# faout.net
KiCad netlist of a schematic drawn in EAGLE
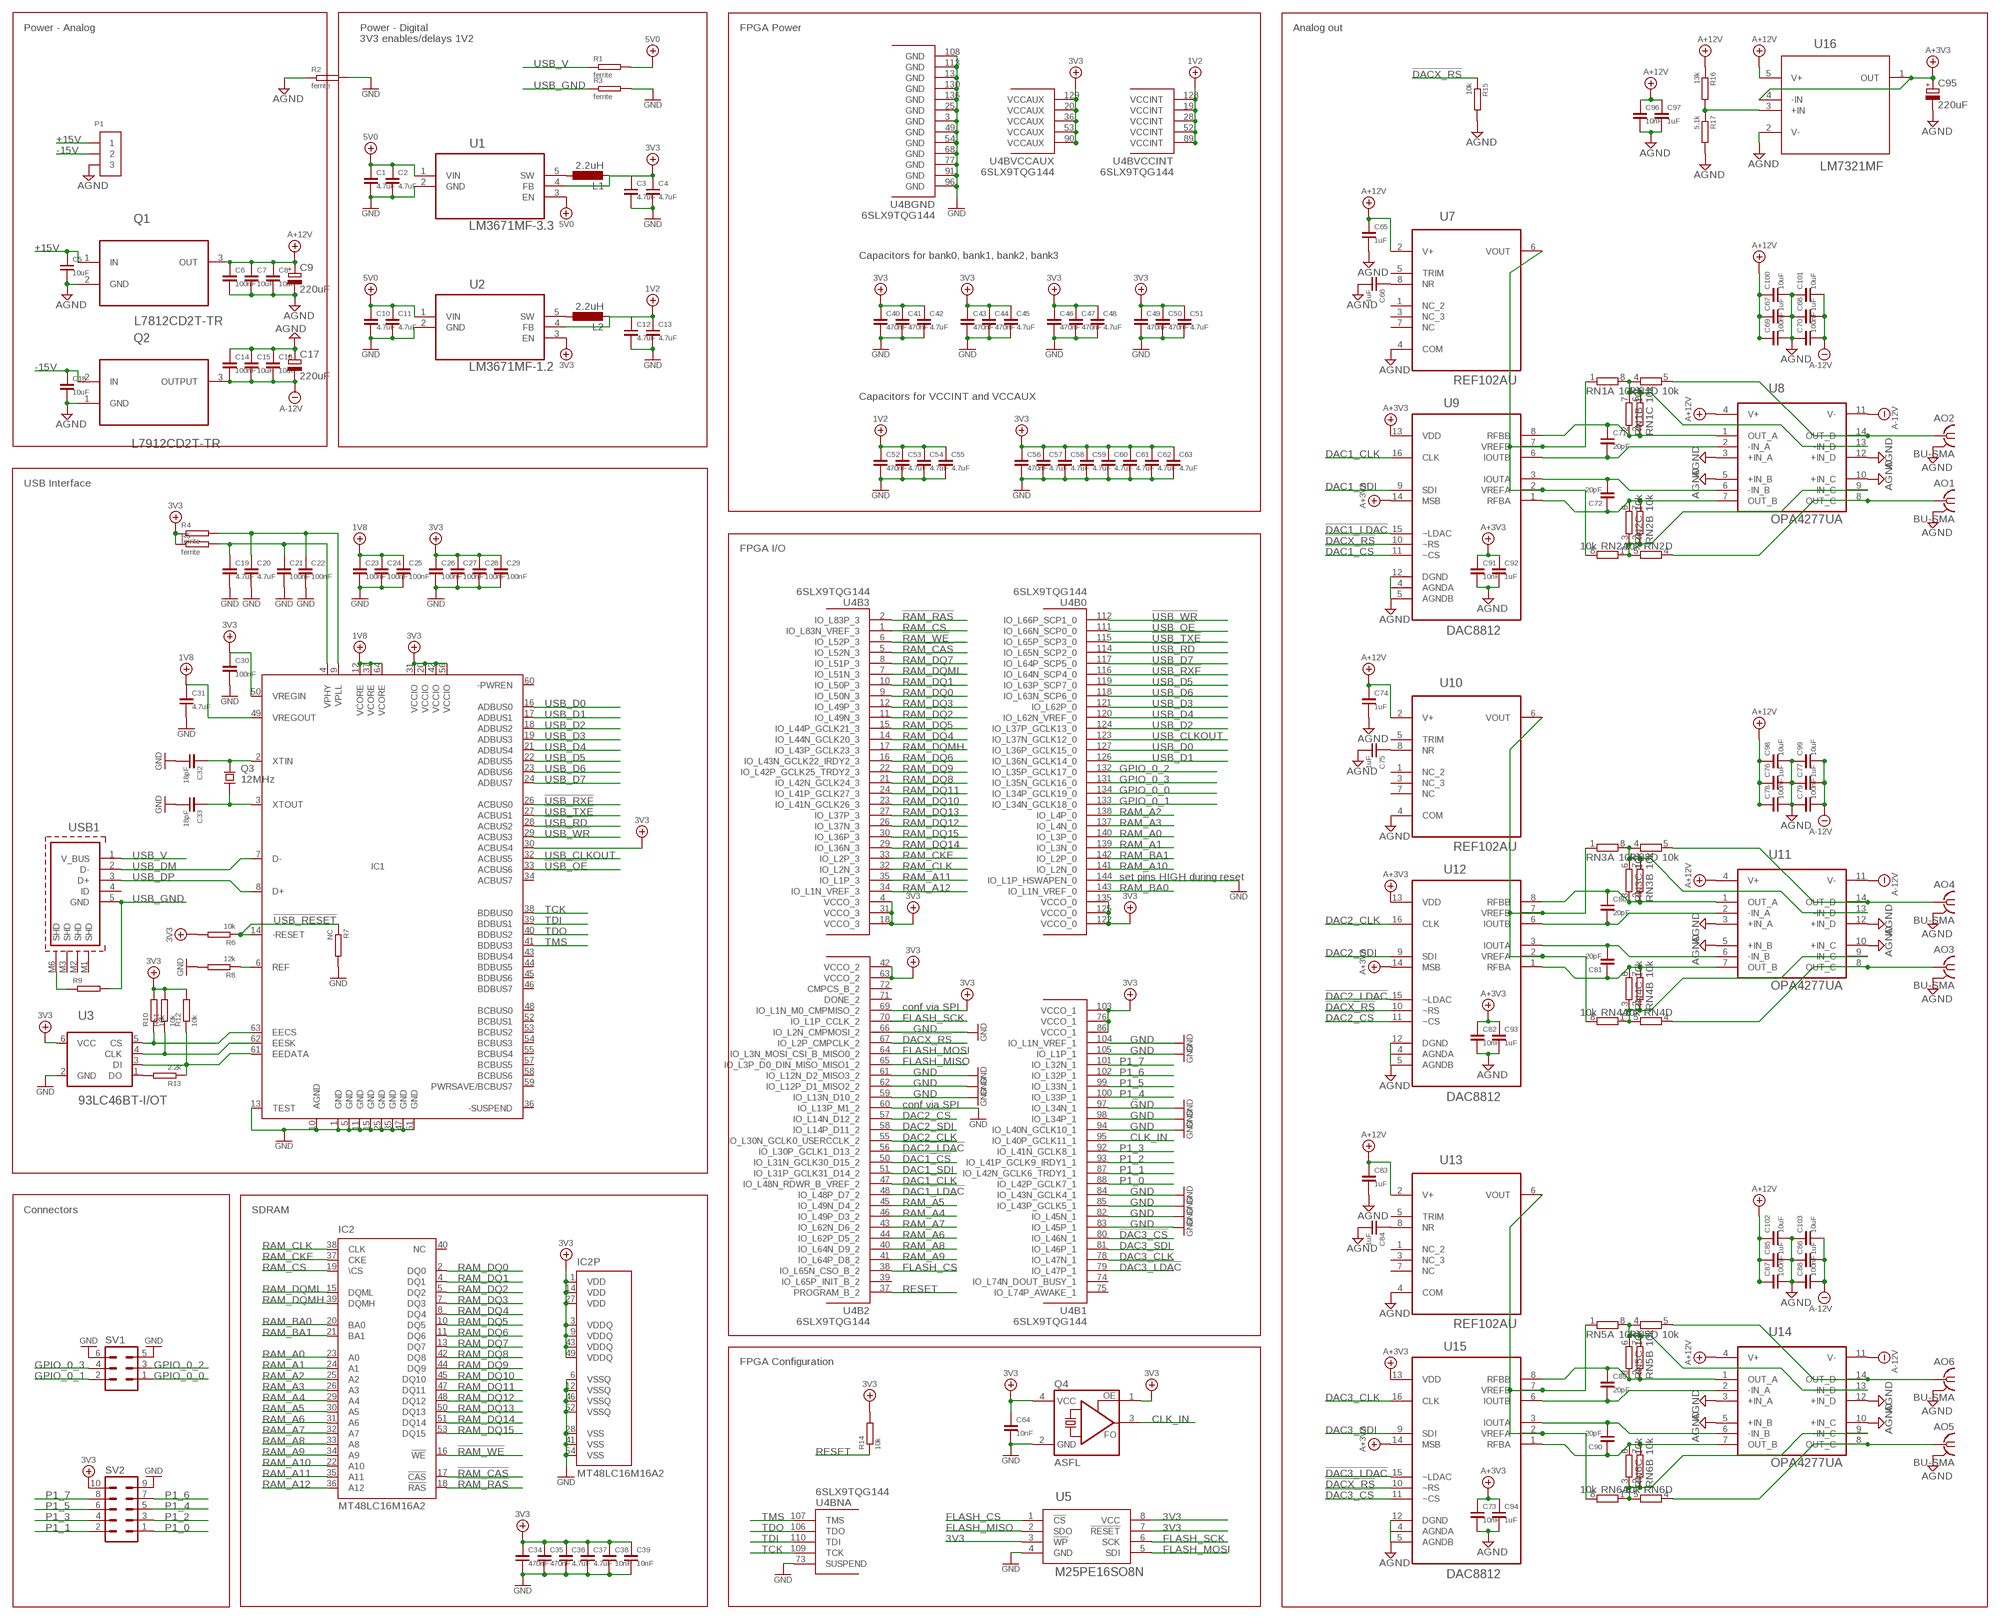
[diagram p0: schematic, sheet 1]

(export (version "E")
  (design (tool "Eeschema 10.0.6"))
  (components
    (comp (ref "AO1")
      (value "BU-SMA")
      (footprint "eagle-import:BU-SMA-H")
      (libsource (lib "eagle-import") (part "BU-SMA"))
    )
    (comp (ref "AO2")
      (value "BU-SMA")
      (footprint "eagle-import:BU-SMA-H")
      (libsource (lib "eagle-import") (part "BU-SMA"))
    )
    (comp (ref "AO3")
      (value "BU-SMA")
      (footprint "eagle-import:BU-SMA-H")
      (libsource (lib "eagle-import") (part "BU-SMA"))
    )
    (comp (ref "AO4")
      (value "BU-SMA")
      (footprint "eagle-import:BU-SMA-H")
      (libsource (lib "eagle-import") (part "BU-SMA"))
    )
    (comp (ref "AO5")
      (value "BU-SMA")
      (footprint "eagle-import:BU-SMA-H")
      (libsource (lib "eagle-import") (part "BU-SMA"))
    )
    (comp (ref "AO6")
      (value "BU-SMA")
      (footprint "eagle-import:BU-SMA-H")
      (libsource (lib "eagle-import") (part "BU-SMA"))
    )
    (comp (ref "C1")
      (value "4.7uF")
      (footprint "eagle-import:R0603")
      (libsource (lib "eagle-import") (part "C_EU0603"))
    )
    (comp (ref "C2")
      (value "4.7uF")
      (footprint "eagle-import:R0603")
      (libsource (lib "eagle-import") (part "C_EU0603"))
    )
    (comp (ref "C3")
      (value "4.7uF")
      (footprint "eagle-import:R0603")
      (libsource (lib "eagle-import") (part "C_EU0603"))
    )
    (comp (ref "C4")
      (value "4.7uF")
      (footprint "eagle-import:R0603")
      (libsource (lib "eagle-import") (part "C_EU0603"))
    )
    (comp (ref "C5")
      (value "10uF")
      (footprint "eagle-import:R0805")
      (libsource (lib "eagle-import") (part "C_EU0805"))
    )
    (comp (ref "C6")
      (value "100nF")
      (footprint "eagle-import:R0603")
      (libsource (lib "eagle-import") (part "C_EU0603"))
    )
    (comp (ref "C7")
      (value "10uF")
      (footprint "eagle-import:R0805")
      (libsource (lib "eagle-import") (part "C_EU0805"))
    )
    (comp (ref "C8")
      (value "10uF")
      (footprint "eagle-import:R0805")
      (libsource (lib "eagle-import") (part "C_EU0805"))
    )
    (comp (ref "C9")
      (value "220uF")
      (footprint "eagle-import:PANASONIC_E")
      (libsource (lib "eagle-import") (part "CPOL-EUE"))
    )
    (comp (ref "C10")
      (value "4.7uF")
      (footprint "eagle-import:R0603")
      (libsource (lib "eagle-import") (part "C_EU0603"))
    )
    (comp (ref "C11")
      (value "4.7uF")
      (footprint "eagle-import:R0603")
      (libsource (lib "eagle-import") (part "C_EU0603"))
    )
    (comp (ref "C12")
      (value "4.7uF")
      (footprint "eagle-import:R0603")
      (libsource (lib "eagle-import") (part "C_EU0603"))
    )
    (comp (ref "C13")
      (value "4.7uF")
      (footprint "eagle-import:R0603")
      (libsource (lib "eagle-import") (part "C_EU0603"))
    )
    (comp (ref "C14")
      (value "100nF")
      (footprint "eagle-import:R0603")
      (libsource (lib "eagle-import") (part "C_EU0603"))
    )
    (comp (ref "C15")
      (value "10uF")
      (footprint "eagle-import:R0805")
      (libsource (lib "eagle-import") (part "C_EU0805"))
    )
    (comp (ref "C16")
      (value "10uF")
      (footprint "eagle-import:R0805")
      (libsource (lib "eagle-import") (part "C_EU0805"))
    )
    (comp (ref "C17")
      (value "220uF")
      (footprint "eagle-import:PANASONIC_E")
      (libsource (lib "eagle-import") (part "CPOL-EUE"))
    )
    (comp (ref "C18")
      (value "10uF")
      (footprint "eagle-import:R0805")
      (libsource (lib "eagle-import") (part "C_EU0805"))
    )
    (comp (ref "C19")
      (value "4.7uF")
      (footprint "eagle-import:R0603")
      (libsource (lib "eagle-import") (part "C_EU0603"))
    )
    (comp (ref "C20")
      (value "4.7uF")
      (footprint "eagle-import:R0603")
      (libsource (lib "eagle-import") (part "C_EU0603"))
    )
    (comp (ref "C21")
      (value "100nF")
      (footprint "eagle-import:R0603")
      (libsource (lib "eagle-import") (part "C_EU0603"))
    )
    (comp (ref "C22")
      (value "100nF")
      (footprint "eagle-import:R0603")
      (libsource (lib "eagle-import") (part "C_EU0603"))
    )
    (comp (ref "C23")
      (value "100nF")
      (footprint "eagle-import:R0603")
      (libsource (lib "eagle-import") (part "C_EU0603"))
    )
    (comp (ref "C24")
      (value "100nF")
      (footprint "eagle-import:R0603")
      (libsource (lib "eagle-import") (part "C_EU0603"))
    )
    (comp (ref "C25")
      (value "100nF")
      (footprint "eagle-import:R0603")
      (libsource (lib "eagle-import") (part "C_EU0603"))
    )
    (comp (ref "C26")
      (value "100nF")
      (footprint "eagle-import:R0603")
      (libsource (lib "eagle-import") (part "C_EU0603"))
    )
    (comp (ref "C27")
      (value "100nF")
      (footprint "eagle-import:R0603")
      (libsource (lib "eagle-import") (part "C_EU0603"))
    )
    (comp (ref "C28")
      (value "100nF")
      (footprint "eagle-import:R0603")
      (libsource (lib "eagle-import") (part "C_EU0603"))
    )
    (comp (ref "C29")
      (value "100nF")
      (footprint "eagle-import:R0603")
      (libsource (lib "eagle-import") (part "C_EU0603"))
    )
    (comp (ref "C30")
      (value "100nF")
      (footprint "eagle-import:R0603")
      (libsource (lib "eagle-import") (part "C_EU0603"))
    )
    (comp (ref "C31")
      (value "4.7uF")
      (footprint "eagle-import:R0603")
      (libsource (lib "eagle-import") (part "C_EU0603"))
    )
    (comp (ref "C32")
      (value "18pF")
      (footprint "eagle-import:R0603")
      (libsource (lib "eagle-import") (part "C_EU0603"))
    )
    (comp (ref "C33")
      (value "18pF")
      (footprint "eagle-import:R0603")
      (libsource (lib "eagle-import") (part "C_EU0603"))
    )
    (comp (ref "C34")
      (value "470nF")
      (footprint "eagle-import:R0603")
      (libsource (lib "eagle-import") (part "C_EU0603"))
    )
    (comp (ref "C35")
      (value "470nF")
      (footprint "eagle-import:R0603")
      (libsource (lib "eagle-import") (part "C_EU0603"))
    )
    (comp (ref "C36")
      (value "4.7uF")
      (footprint "eagle-import:R0603")
      (libsource (lib "eagle-import") (part "C_EU0603"))
    )
    (comp (ref "C37")
      (value "4.7uF")
      (footprint "eagle-import:R0603")
      (libsource (lib "eagle-import") (part "C_EU0603"))
    )
    (comp (ref "C38")
      (value "10nF")
      (footprint "eagle-import:R0603")
      (libsource (lib "eagle-import") (part "C_EU0603"))
    )
    (comp (ref "C39")
      (value "10nF")
      (footprint "eagle-import:R0603")
      (libsource (lib "eagle-import") (part "C_EU0603"))
    )
    (comp (ref "C40")
      (value "470nF")
      (footprint "eagle-import:R0603")
      (libsource (lib "eagle-import") (part "C_EU0603"))
    )
    (comp (ref "C41")
      (value "470nF")
      (footprint "eagle-import:R0603")
      (libsource (lib "eagle-import") (part "C_EU0603"))
    )
    (comp (ref "C42")
      (value "4.7uF")
      (footprint "eagle-import:R0603")
      (libsource (lib "eagle-import") (part "C_EU0603"))
    )
    (comp (ref "C43")
      (value "470nF")
      (footprint "eagle-import:R0603")
      (libsource (lib "eagle-import") (part "C_EU0603"))
    )
    (comp (ref "C44")
      (value "470nF")
      (footprint "eagle-import:R0603")
      (libsource (lib "eagle-import") (part "C_EU0603"))
    )
    (comp (ref "C45")
      (value "4.7uF")
      (footprint "eagle-import:R0603")
      (libsource (lib "eagle-import") (part "C_EU0603"))
    )
    (comp (ref "C46")
      (value "470nF")
      (footprint "eagle-import:R0603")
      (libsource (lib "eagle-import") (part "C_EU0603"))
    )
    (comp (ref "C47")
      (value "470nF")
      (footprint "eagle-import:R0603")
      (libsource (lib "eagle-import") (part "C_EU0603"))
    )
    (comp (ref "C48")
      (value "4.7uF")
      (footprint "eagle-import:R0603")
      (libsource (lib "eagle-import") (part "C_EU0603"))
    )
    (comp (ref "C49")
      (value "470nF")
      (footprint "eagle-import:R0603")
      (libsource (lib "eagle-import") (part "C_EU0603"))
    )
    (comp (ref "C50")
      (value "470nF")
      (footprint "eagle-import:R0603")
      (libsource (lib "eagle-import") (part "C_EU0603"))
    )
    (comp (ref "C51")
      (value "4.7uF")
      (footprint "eagle-import:R0603")
      (libsource (lib "eagle-import") (part "C_EU0603"))
    )
    (comp (ref "C52")
      (value "470nF")
      (footprint "eagle-import:R0603")
      (libsource (lib "eagle-import") (part "C_EU0603"))
    )
    (comp (ref "C53")
      (value "4.7uF")
      (footprint "eagle-import:R0603")
      (libsource (lib "eagle-import") (part "C_EU0603"))
    )
    (comp (ref "C54")
      (value "4.7uF")
      (footprint "eagle-import:R0603")
      (libsource (lib "eagle-import") (part "C_EU0603"))
    )
    (comp (ref "C55")
      (value "4.7uF")
      (footprint "eagle-import:R0603")
      (libsource (lib "eagle-import") (part "C_EU0603"))
    )
    (comp (ref "C56")
      (value "470nF")
      (footprint "eagle-import:R0603")
      (libsource (lib "eagle-import") (part "C_EU0603"))
    )
    (comp (ref "C57")
      (value "4.7uF")
      (footprint "eagle-import:R0603")
      (libsource (lib "eagle-import") (part "C_EU0603"))
    )
    (comp (ref "C58")
      (value "4.7uF")
      (footprint "eagle-import:R0603")
      (libsource (lib "eagle-import") (part "C_EU0603"))
    )
    (comp (ref "C59")
      (value "4.7uF")
      (footprint "eagle-import:R0603")
      (libsource (lib "eagle-import") (part "C_EU0603"))
    )
    (comp (ref "C60")
      (value "4.7uF")
      (footprint "eagle-import:R0603")
      (libsource (lib "eagle-import") (part "C_EU0603"))
    )
    (comp (ref "C61")
      (value "4.7uF")
      (footprint "eagle-import:R0603")
      (libsource (lib "eagle-import") (part "C_EU0603"))
    )
    (comp (ref "C62")
      (value "4.7uF")
      (footprint "eagle-import:R0603")
      (libsource (lib "eagle-import") (part "C_EU0603"))
    )
    (comp (ref "C63")
      (value "4.7uF")
      (footprint "eagle-import:R0603")
      (libsource (lib "eagle-import") (part "C_EU0603"))
    )
    (comp (ref "C64")
      (value "10nF")
      (footprint "eagle-import:R0603")
      (libsource (lib "eagle-import") (part "C_EU0603"))
    )
    (comp (ref "C65")
      (value "1uF")
      (footprint "eagle-import:R0603")
      (libsource (lib "eagle-import") (part "C_EU0603"))
    )
    (comp (ref "C66")
      (value "1uF")
      (footprint "eagle-import:R0603")
      (libsource (lib "eagle-import") (part "C_EU0603"))
    )
    (comp (ref "C67")
      (value "1uF")
      (footprint "eagle-import:R0603")
      (libsource (lib "eagle-import") (part "C_EU0603"))
    )
    (comp (ref "C68")
      (value "1uF")
      (footprint "eagle-import:R0603")
      (libsource (lib "eagle-import") (part "C_EU0603"))
    )
    (comp (ref "C69")
      (value "100nF")
      (footprint "eagle-import:R0603")
      (libsource (lib "eagle-import") (part "C_EU0603"))
    )
    (comp (ref "C70")
      (value "100nF")
      (footprint "eagle-import:R0603")
      (libsource (lib "eagle-import") (part "C_EU0603"))
    )
    (comp (ref "C71")
      (value "20pF")
      (footprint "eagle-import:R0603")
      (libsource (lib "eagle-import") (part "C_EU0603"))
    )
    (comp (ref "C72")
      (value "20pF")
      (footprint "eagle-import:R0603")
      (libsource (lib "eagle-import") (part "C_EU0603"))
    )
    (comp (ref "C73")
      (value "10nF")
      (footprint "eagle-import:R0603")
      (libsource (lib "eagle-import") (part "C_EU0603"))
    )
    (comp (ref "C74")
      (value "1uF")
      (footprint "eagle-import:R0603")
      (libsource (lib "eagle-import") (part "C_EU0603"))
    )
    (comp (ref "C75")
      (value "1uF")
      (footprint "eagle-import:R0603")
      (libsource (lib "eagle-import") (part "C_EU0603"))
    )
    (comp (ref "C76")
      (value "1uF")
      (footprint "eagle-import:R0603")
      (libsource (lib "eagle-import") (part "C_EU0603"))
    )
    (comp (ref "C77")
      (value "1uF")
      (footprint "eagle-import:R0603")
      (libsource (lib "eagle-import") (part "C_EU0603"))
    )
    (comp (ref "C78")
      (value "100nF")
      (footprint "eagle-import:R0603")
      (libsource (lib "eagle-import") (part "C_EU0603"))
    )
    (comp (ref "C79")
      (value "100nF")
      (footprint "eagle-import:R0603")
      (libsource (lib "eagle-import") (part "C_EU0603"))
    )
    (comp (ref "C80")
      (value "20pF")
      (footprint "eagle-import:R0603")
      (libsource (lib "eagle-import") (part "C_EU0603"))
    )
    (comp (ref "C81")
      (value "20pF")
      (footprint "eagle-import:R0603")
      (libsource (lib "eagle-import") (part "C_EU0603"))
    )
    (comp (ref "C82")
      (value "10nF")
      (footprint "eagle-import:R0603")
      (libsource (lib "eagle-import") (part "C_EU0603"))
    )
    (comp (ref "C83")
      (value "1uF")
      (footprint "eagle-import:R0603")
      (libsource (lib "eagle-import") (part "C_EU0603"))
    )
    (comp (ref "C84")
      (value "1uF")
      (footprint "eagle-import:R0603")
      (libsource (lib "eagle-import") (part "C_EU0603"))
    )
    (comp (ref "C85")
      (value "1uF")
      (footprint "eagle-import:R0603")
      (libsource (lib "eagle-import") (part "C_EU0603"))
    )
    (comp (ref "C86")
      (value "1uF")
      (footprint "eagle-import:R0603")
      (libsource (lib "eagle-import") (part "C_EU0603"))
    )
    (comp (ref "C87")
      (value "100nF")
      (footprint "eagle-import:R0603")
      (libsource (lib "eagle-import") (part "C_EU0603"))
    )
    (comp (ref "C88")
      (value "100nF")
      (footprint "eagle-import:R0603")
      (libsource (lib "eagle-import") (part "C_EU0603"))
    )
    (comp (ref "C89")
      (value "20pF")
      (footprint "eagle-import:R0603")
      (libsource (lib "eagle-import") (part "C_EU0603"))
    )
    (comp (ref "C90")
      (value "20pF")
      (footprint "eagle-import:R0603")
      (libsource (lib "eagle-import") (part "C_EU0603"))
    )
    (comp (ref "C91")
      (value "10nF")
      (footprint "eagle-import:R0603")
      (libsource (lib "eagle-import") (part "C_EU0603"))
    )
    (comp (ref "C92")
      (value "1uF")
      (footprint "eagle-import:R0603")
      (libsource (lib "eagle-import") (part "C_EU0603"))
    )
    (comp (ref "C93")
      (value "1uF")
      (footprint "eagle-import:R0603")
      (libsource (lib "eagle-import") (part "C_EU0603"))
    )
    (comp (ref "C94")
      (value "1uF")
      (footprint "eagle-import:R0603")
      (libsource (lib "eagle-import") (part "C_EU0603"))
    )
    (comp (ref "C95")
      (value "220uF")
      (footprint "eagle-import:PANASONIC_E")
      (libsource (lib "eagle-import") (part "CPOL-EUE"))
    )
    (comp (ref "C96")
      (value "10nF")
      (footprint "eagle-import:R0603")
      (libsource (lib "eagle-import") (part "C_EU0603"))
    )
    (comp (ref "C97")
      (value "1uF")
      (footprint "eagle-import:R0603")
      (libsource (lib "eagle-import") (part "C_EU0603"))
    )
    (comp (ref "C98")
      (value "10uF")
      (footprint "eagle-import:R0805")
      (libsource (lib "eagle-import") (part "C_EU0805"))
    )
    (comp (ref "C99")
      (value "10uF")
      (footprint "eagle-import:R0805")
      (libsource (lib "eagle-import") (part "C_EU0805"))
    )
    (comp (ref "C100")
      (value "10uF")
      (footprint "eagle-import:R0805")
      (libsource (lib "eagle-import") (part "C_EU0805"))
    )
    (comp (ref "C101")
      (value "10uF")
      (footprint "eagle-import:R0805")
      (libsource (lib "eagle-import") (part "C_EU0805"))
    )
    (comp (ref "C102")
      (value "10uF")
      (footprint "eagle-import:R0805")
      (libsource (lib "eagle-import") (part "C_EU0805"))
    )
    (comp (ref "C103")
      (value "10uF")
      (footprint "eagle-import:R0805")
      (libsource (lib "eagle-import") (part "C_EU0805"))
    )
    (comp (ref "IC1")
      (value "FT2232HL")
      (footprint "eagle-import:TQFP64-12X12")
      (libsource (lib "eagle-import") (part "FT2232HL"))
    )
    (comp (ref "IC2")
      (value "MT48LC16M16A2")
      (footprint "eagle-import:TSOP54-400")
      (libsource (lib "eagle-import") (part "MT48LC16M16A2"))
    )
    (comp (ref "L1")
      (value "2.2uH")
      (footprint "eagle-import:L5038P")
      (libsource (lib "eagle-import") (part "L-EUL5038P"))
    )
    (comp (ref "L2")
      (value "2.2uH")
      (footprint "eagle-import:L5038P")
      (libsource (lib "eagle-import") (part "L-EUL5038P"))
    )
    (comp (ref "P1")
      (value "TE_CONN_MTE_HEADER3R")
      (footprint "eagle-import:TE_CONN_MTE_HEADER3_R")
      (libsource (lib "eagle-import") (part "TE_CONN_MTE_HEADER3R"))
    )
    (comp (ref "Q1")
      (value "L7812CD2T-TR")
      (footprint "eagle-import:TO254P1524X460-3N")
      (fields (field (name "OC_FARNELL") "2296017"))
      (libsource (lib "eagle-import") (part "L7812CD2T-TR"))
    )
    (comp (ref "Q2")
      (value "L7912CD2T-TR")
      (footprint "eagle-import:TO254P1524X460-3N")
      (libsource (lib "eagle-import") (part "L7912CD2T-TR"))
    )
    (comp (ref "Q3")
      (value "12MHz")
      (footprint "eagle-import:TXC_QUARTZ_7A")
      (libsource (lib "eagle-import") (part "TXC_QUARTZ_7A"))
    )
    (comp (ref "Q4")
      (value "ASFL")
      (footprint "eagle-import:ASF")
      (fields (field (name "MPN") "ASFLM1-50.000MHZ-C-T"))
      (libsource (lib "eagle-import") (part "ASFL"))
    )
    (comp (ref "R1")
      (value "ferrite")
      (footprint "eagle-import:R1206")
      (libsource (lib "eagle-import") (part "R_EU1206"))
    )
    (comp (ref "R2")
      (value "ferrite")
      (footprint "eagle-import:R1206")
      (libsource (lib "eagle-import") (part "R_EU1206"))
    )
    (comp (ref "R3")
      (value "ferrite")
      (footprint "eagle-import:R1206")
      (libsource (lib "eagle-import") (part "R_EU1206"))
    )
    (comp (ref "R4")
      (value "ferrite")
      (footprint "eagle-import:R0603")
      (libsource (lib "eagle-import") (part "R_EU0603"))
    )
    (comp (ref "R5")
      (value "ferrite")
      (footprint "eagle-import:R0603")
      (libsource (lib "eagle-import") (part "R_EU0603"))
    )
    (comp (ref "R6")
      (value "10k")
      (footprint "eagle-import:R0603")
      (libsource (lib "eagle-import") (part "R_EU0603"))
    )
    (comp (ref "R7")
      (value "NC")
      (footprint "eagle-import:R0603")
      (libsource (lib "eagle-import") (part "R_EU0603"))
    )
    (comp (ref "R8")
      (value "12k")
      (footprint "eagle-import:R0603")
      (libsource (lib "eagle-import") (part "R_EU0603"))
    )
    (comp (ref "R9")
      (value "R_EU0603")
      (footprint "eagle-import:R0603")
      (libsource (lib "eagle-import") (part "R_EU0603"))
    )
    (comp (ref "R10")
      (value "10k")
      (footprint "eagle-import:R0603")
      (libsource (lib "eagle-import") (part "R_EU0603"))
    )
    (comp (ref "R11")
      (value "10k")
      (footprint "eagle-import:R0603")
      (libsource (lib "eagle-import") (part "R_EU0603"))
    )
    (comp (ref "R12")
      (value "10k")
      (footprint "eagle-import:R0603")
      (libsource (lib "eagle-import") (part "R_EU0603"))
    )
    (comp (ref "R13")
      (value "2.2k")
      (footprint "eagle-import:R0603")
      (libsource (lib "eagle-import") (part "R_EU0603"))
    )
    (comp (ref "R14")
      (value "10k")
      (footprint "eagle-import:R0603")
      (libsource (lib "eagle-import") (part "R_EU0603"))
    )
    (comp (ref "R15")
      (value "10k")
      (footprint "eagle-import:R0603")
      (libsource (lib "eagle-import") (part "R_EU0603"))
    )
    (comp (ref "R16")
      (value "13k")
      (footprint "eagle-import:R0603")
      (libsource (lib "eagle-import") (part "R_EU0603"))
    )
    (comp (ref "R17")
      (value "5.1k")
      (footprint "eagle-import:R0603")
      (libsource (lib "eagle-import") (part "R_EU0603"))
    )
    (comp (ref "RN1")
      (value "10k")
      (footprint "eagle-import:EXBV8V")
      (fields (field (name "OC_FARNELL") "1560925"))
      (libsource (lib "eagle-import") (part "4R-NEXBV8V"))
    )
    (comp (ref "RN2")
      (value "10k")
      (footprint "eagle-import:EXBV8V")
      (fields (field (name "OC_FARNELL") "1560925"))
      (libsource (lib "eagle-import") (part "4R-NEXBV8V"))
    )
    (comp (ref "RN3")
      (value "10k")
      (footprint "eagle-import:EXBV8V")
      (fields (field (name "OC_FARNELL") "1560925"))
      (libsource (lib "eagle-import") (part "4R-NEXBV8V"))
    )
    (comp (ref "RN4")
      (value "10k")
      (footprint "eagle-import:EXBV8V")
      (fields (field (name "OC_FARNELL") "1560925"))
      (libsource (lib "eagle-import") (part "4R-NEXBV8V"))
    )
    (comp (ref "RN5")
      (value "10k")
      (footprint "eagle-import:EXBV8V")
      (fields (field (name "OC_FARNELL") "1560925"))
      (libsource (lib "eagle-import") (part "4R-NEXBV8V"))
    )
    (comp (ref "RN6")
      (value "10k")
      (footprint "eagle-import:EXBV8V")
      (fields (field (name "OC_FARNELL") "1560925"))
      (libsource (lib "eagle-import") (part "4R-NEXBV8V"))
    )
    (comp (ref "SV1")
      (value "ML6L")
      (footprint "eagle-import:ML6L")
      (fields (field (name "OC_FARNELL") "2356262"))
      (libsource (lib "eagle-import") (part "ML6L"))
    )
    (comp (ref "SV2")
      (value "ML10")
      (footprint "eagle-import:ML10")
      (libsource (lib "eagle-import") (part "ML10"))
    )
    (comp (ref "U1")
      (value "LM3671MF-3.3")
      (footprint "eagle-import:SOT95P284X122-5N")
      (libsource (lib "eagle-import") (part "LM3671MF-3.3"))
    )
    (comp (ref "U2")
      (value "LM3671MF-1.2")
      (footprint "eagle-import:SOT95P284X122-5N")
      (libsource (lib "eagle-import") (part "LM3671MF-1.2"))
    )
    (comp (ref "U3")
      (value "93LC46BT-I/OT")
      (footprint "eagle-import:SOT95P280X145-6N")
      (libsource (lib "eagle-import") (part "93LC46BT-I/OT"))
    )
    (comp (ref "U4")
      (value "6SLX9TQG144")
      (footprint "eagle-import:TQ144")
      (fields (field (name "OC_FARNELL") "1876228"))
      (libsource (lib "eagle-import") (part "6SLX9TQG144"))
    )
    (comp (ref "U5")
      (value "M25PE16SO8N")
      (footprint "eagle-import:SOIC127P600X175-8N")
      (libsource (lib "eagle-import") (part "M25PE16SO8N"))
    )
    (comp (ref "U7")
      (value "REF102AU")
      (footprint "eagle-import:SOIC127P600X175-8N")
      (libsource (lib "eagle-import") (part "REF102AU"))
    )
    (comp (ref "U8")
      (value "OPA4277UA")
      (footprint "eagle-import:SOIC127P600X175-14N")
      (libsource (lib "eagle-import") (part "OPA4277UA"))
    )
    (comp (ref "U9")
      (value "DAC8812")
      (footprint "eagle-import:SOP65P640X120-16N")
      (libsource (lib "eagle-import") (part "DAC8812"))
    )
    (comp (ref "U10")
      (value "REF102AU")
      (footprint "eagle-import:SOIC127P600X175-8N")
      (libsource (lib "eagle-import") (part "REF102AU"))
    )
    (comp (ref "U11")
      (value "OPA4277UA")
      (footprint "eagle-import:SOIC127P600X175-14N")
      (libsource (lib "eagle-import") (part "OPA4277UA"))
    )
    (comp (ref "U12")
      (value "DAC8812")
      (footprint "eagle-import:SOP65P640X120-16N")
      (libsource (lib "eagle-import") (part "DAC8812"))
    )
    (comp (ref "U13")
      (value "REF102AU")
      (footprint "eagle-import:SOIC127P600X175-8N")
      (libsource (lib "eagle-import") (part "REF102AU"))
    )
    (comp (ref "U14")
      (value "OPA4277UA")
      (footprint "eagle-import:SOIC127P600X175-14N")
      (libsource (lib "eagle-import") (part "OPA4277UA"))
    )
    (comp (ref "U15")
      (value "DAC8812")
      (footprint "eagle-import:SOP65P640X120-16N")
      (libsource (lib "eagle-import") (part "DAC8812"))
    )
    (comp (ref "U16")
      (value "LM7321MF")
      (footprint "eagle-import:SOT95P300X120-5N")
      (libsource (lib "eagle-import") (part "LM7321MF"))
    )
    (comp (ref "USB1")
      (value "MOLEX_USB_105017-0001")
      (footprint "eagle-import:MOLEX_105017-0001")
      (libsource (lib "eagle-import") (part "MOLEX_USB_105017-0001"))
    )
  )
  (nets
    (net (code "1") (name "/+15V") (class "Default")
      (node (ref "C5") (pin "1") (pinfunction "P$1_1") (pintype "passive"))
      (node (ref "P1") (pin "P$1") (pinfunction "1_P$1") (pintype "bidirectional"))
      (node (ref "Q1") (pin "1") (pinfunction "IN_1") (pintype "input"))
    )
    (net (code "2") (name "/-15V") (class "Default")
      (node (ref "C18") (pin "1") (pinfunction "P$1_1") (pintype "passive"))
      (node (ref "P1") (pin "P$2") (pinfunction "2_P$2") (pintype "bidirectional"))
      (node (ref "Q2") (pin "2") (pinfunction "IN_2") (pintype "input"))
    )
    (net (code "3") (name "/CLK_IN") (class "Default")
      (node (ref "Q4") (pin "3") (pinfunction "FO_3") (pintype "output"))
      (node (ref "U4") (pin "95") (pinfunction "IO_L40P_GCLK11_1_95") (pintype "bidirectional"))
    )
    (net (code "4") (name "/DAC1_CLK") (class "Default")
      (node (ref "U4") (pin "47") (pinfunction "IO_L48N_RDWR_B_VREF_2_47") (pintype "bidirectional"))
      (node (ref "U9") (pin "16") (pinfunction "CLK_16") (pintype "input"))
    )
    (net (code "5") (name "/DAC1_SDI") (class "Default")
      (node (ref "U4") (pin "51") (pinfunction "IO_L31P_GCLK31_D14_2_51") (pintype "bidirectional"))
      (node (ref "U9") (pin "9") (pinfunction "SDI_9") (pintype "input"))
    )
    (net (code "6") (name "/DAC2_CLK") (class "Default")
      (node (ref "U12") (pin "16") (pinfunction "CLK_16") (pintype "input"))
      (node (ref "U4") (pin "55") (pinfunction "IO_L30N_GCLK0_USERCCLK_2_55") (pintype "bidirectional"))
    )
    (net (code "7") (name "/DAC2_SDI") (class "Default")
      (node (ref "U12") (pin "9") (pinfunction "SDI_9") (pintype "input"))
      (node (ref "U4") (pin "58") (pinfunction "IO_L14P_D11_2_58") (pintype "bidirectional"))
    )
    (net (code "8") (name "/DAC3_CLK") (class "Default")
      (node (ref "U15") (pin "16") (pinfunction "CLK_16") (pintype "input"))
      (node (ref "U4") (pin "78") (pinfunction "IO_L47N_1_78") (pintype "bidirectional"))
    )
    (net (code "9") (name "/DAC3_SDI") (class "Default")
      (node (ref "U15") (pin "9") (pinfunction "SDI_9") (pintype "input"))
      (node (ref "U4") (pin "81") (pinfunction "IO_L46P_1_81") (pintype "bidirectional"))
    )
    (net (code "10") (name "/FLASH_CS") (class "Default")
      (node (ref "U4") (pin "38") (pinfunction "IO_L65N_CSO_B_2_38") (pintype "bidirectional"))
      (node (ref "U5") (pin "1") (pinfunction "~{CS}_1") (pintype "input"))
    )
    (net (code "11") (name "/FLASH_MISO") (class "Default")
      (node (ref "U4") (pin "65") (pinfunction "IO_L3P_D0_DIN_MISO_MISO1_2_65") (pintype "bidirectional"))
      (node (ref "U5") (pin "2") (pinfunction "SDO_2") (pintype "output"))
    )
    (net (code "12") (name "/FLASH_MOSI") (class "Default")
      (node (ref "U4") (pin "64") (pinfunction "IO_L3N_MOSI_CSI_B_MISO0_2_64") (pintype "bidirectional"))
      (node (ref "U5") (pin "5") (pinfunction "SDI_5") (pintype "input"))
    )
    (net (code "13") (name "/FLASH_SCK") (class "Default")
      (node (ref "U4") (pin "70") (pinfunction "IO_L1P_CCLK_2_70") (pintype "bidirectional"))
      (node (ref "U5") (pin "6") (pinfunction "SCK_6") (pintype "input"))
    )
    (net (code "14") (name "/GPIO_0_0") (class "Default")
      (node (ref "SV1") (pin "1") (pinfunction "1_1") (pintype "passive"))
      (node (ref "U4") (pin "134") (pinfunction "IO_L34P_GCLK19_0_134") (pintype "bidirectional"))
    )
    (net (code "15") (name "/GPIO_0_1") (class "Default")
      (node (ref "SV1") (pin "2") (pinfunction "2_2") (pintype "passive"))
      (node (ref "U4") (pin "133") (pinfunction "IO_L34N_GCLK18_0_133") (pintype "bidirectional"))
    )
    (net (code "16") (name "/GPIO_0_2") (class "Default")
      (node (ref "SV1") (pin "3") (pinfunction "3_3") (pintype "passive"))
      (node (ref "U4") (pin "132") (pinfunction "IO_L35P_GCLK17_0_132") (pintype "bidirectional"))
    )
    (net (code "17") (name "/GPIO_0_3") (class "Default")
      (node (ref "SV1") (pin "4") (pinfunction "4_4") (pintype "passive"))
      (node (ref "U4") (pin "131") (pinfunction "IO_L35N_GCLK16_0_131") (pintype "bidirectional"))
    )
    (net (code "18") (name "/P1_0") (class "Default")
      (node (ref "SV2") (pin "1") (pinfunction "1_1") (pintype "passive"))
      (node (ref "U4") (pin "88") (pinfunction "IO_L42P_GCLK7_1_88") (pintype "bidirectional"))
    )
    (net (code "19") (name "/P1_1") (class "Default")
      (node (ref "SV2") (pin "2") (pinfunction "2_2") (pintype "passive"))
      (node (ref "U4") (pin "87") (pinfunction "IO_L42N_GCLK6_TRDY1_1_87") (pintype "bidirectional"))
    )
    (net (code "20") (name "/P1_2") (class "Default")
      (node (ref "SV2") (pin "3") (pinfunction "3_3") (pintype "passive"))
      (node (ref "U4") (pin "93") (pinfunction "IO_L41P_GCLK9_IRDY1_1_93") (pintype "bidirectional"))
    )
    (net (code "21") (name "/P1_3") (class "Default")
      (node (ref "SV2") (pin "4") (pinfunction "4_4") (pintype "passive"))
      (node (ref "U4") (pin "92") (pinfunction "IO_L41N_GCLK8_1_92") (pintype "bidirectional"))
    )
    (net (code "22") (name "/P1_4") (class "Default")
      (node (ref "SV2") (pin "5") (pinfunction "5_5") (pintype "passive"))
      (node (ref "U4") (pin "100") (pinfunction "IO_L33P_1_100") (pintype "bidirectional"))
    )
    (net (code "23") (name "/P1_5") (class "Default")
      (node (ref "SV2") (pin "6") (pinfunction "6_6") (pintype "passive"))
      (node (ref "U4") (pin "99") (pinfunction "IO_L33N_1_99") (pintype "bidirectional"))
    )
    (net (code "24") (name "/P1_6") (class "Default")
      (node (ref "SV2") (pin "7") (pinfunction "7_7") (pintype "passive"))
      (node (ref "U4") (pin "102") (pinfunction "IO_L32P_1_102") (pintype "bidirectional"))
    )
    (net (code "25") (name "/P1_7") (class "Default")
      (node (ref "SV2") (pin "8") (pinfunction "8_8") (pintype "passive"))
      (node (ref "U4") (pin "101") (pinfunction "IO_L32N_1_101") (pintype "bidirectional"))
    )
    (net (code "26") (name "/RAM_A0") (class "Default")
      (node (ref "IC2") (pin "23") (pinfunction "A0_23") (pintype "input"))
      (node (ref "U4") (pin "140") (pinfunction "IO_L3P_0_140") (pintype "bidirectional"))
    )
    (net (code "27") (name "/RAM_A1") (class "Default")
      (node (ref "IC2") (pin "24") (pinfunction "A1_24") (pintype "input"))
      (node (ref "U4") (pin "139") (pinfunction "IO_L3N_0_139") (pintype "bidirectional"))
    )
    (net (code "28") (name "/RAM_A2") (class "Default")
      (node (ref "IC2") (pin "25") (pinfunction "A2_25") (pintype "input"))
      (node (ref "U4") (pin "138") (pinfunction "IO_L4P_0_138") (pintype "bidirectional"))
    )
    (net (code "29") (name "/RAM_A3") (class "Default")
      (node (ref "IC2") (pin "26") (pinfunction "A3_26") (pintype "input"))
      (node (ref "U4") (pin "137") (pinfunction "IO_L4N_0_137") (pintype "bidirectional"))
    )
    (net (code "30") (name "/RAM_A4") (class "Default")
      (node (ref "IC2") (pin "29") (pinfunction "A4_29") (pintype "input"))
      (node (ref "U4") (pin "46") (pinfunction "IO_L49P_D3_2_46") (pintype "bidirectional"))
    )
    (net (code "31") (name "/RAM_A5") (class "Default")
      (node (ref "IC2") (pin "30") (pinfunction "A5_30") (pintype "input"))
      (node (ref "U4") (pin "45") (pinfunction "IO_L49N_D4_2_45") (pintype "bidirectional"))
    )
    (net (code "32") (name "/RAM_A6") (class "Default")
      (node (ref "IC2") (pin "31") (pinfunction "A6_31") (pintype "input"))
      (node (ref "U4") (pin "44") (pinfunction "IO_L62P_D5_2_44") (pintype "bidirectional"))
    )
    (net (code "33") (name "/RAM_A7") (class "Default")
      (node (ref "IC2") (pin "32") (pinfunction "A7_32") (pintype "input"))
      (node (ref "U4") (pin "43") (pinfunction "IO_L62N_D6_2_43") (pintype "bidirectional"))
    )
    (net (code "34") (name "/RAM_A8") (class "Default")
      (node (ref "IC2") (pin "33") (pinfunction "A8_33") (pintype "input"))
      (node (ref "U4") (pin "40") (pinfunction "IO_L64N_D9_2_40") (pintype "bidirectional"))
    )
    (net (code "35") (name "/RAM_A9") (class "Default")
      (node (ref "IC2") (pin "34") (pinfunction "A9_34") (pintype "input"))
      (node (ref "U4") (pin "41") (pinfunction "IO_L64P_D8_2_41") (pintype "bidirectional"))
    )
    (net (code "36") (name "/RAM_A10") (class "Default")
      (node (ref "IC2") (pin "22") (pinfunction "A10_22") (pintype "input"))
      (node (ref "U4") (pin "141") (pinfunction "IO_L2N_0_141") (pintype "bidirectional"))
    )
    (net (code "37") (name "/RAM_A11") (class "Default")
      (node (ref "IC2") (pin "35") (pinfunction "A11_35") (pintype "input"))
      (node (ref "U4") (pin "35") (pinfunction "IO_L1P_3_35") (pintype "bidirectional"))
    )
    (net (code "38") (name "/RAM_A12") (class "Default")
      (node (ref "IC2") (pin "36") (pinfunction "A12_36") (pintype "input"))
      (node (ref "U4") (pin "34") (pinfunction "IO_L1N_VREF_3_34") (pintype "bidirectional"))
    )
    (net (code "39") (name "/RAM_BA0") (class "Default")
      (node (ref "IC2") (pin "20") (pinfunction "BA0_20") (pintype "input"))
      (node (ref "U4") (pin "143") (pinfunction "IO_L1N_VREF_0_143") (pintype "bidirectional"))
    )
    (net (code "40") (name "/RAM_BA1") (class "Default")
      (node (ref "IC2") (pin "21") (pinfunction "BA1_21") (pintype "input"))
      (node (ref "U4") (pin "142") (pinfunction "IO_L2P_0_142") (pintype "bidirectional"))
    )
    (net (code "41") (name "/RAM_CKE") (class "Default")
      (node (ref "IC2") (pin "37") (pinfunction "CKE_37") (pintype "input"))
      (node (ref "U4") (pin "33") (pinfunction "IO_L2P_3_33") (pintype "bidirectional"))
    )
    (net (code "42") (name "/RAM_CLK") (class "Default")
      (node (ref "IC2") (pin "38") (pinfunction "CLK_38") (pintype "input"))
      (node (ref "U4") (pin "32") (pinfunction "IO_L2N_3_32") (pintype "bidirectional"))
    )
    (net (code "43") (name "/RAM_CS") (class "Default")
      (node (ref "IC2") (pin "19") (pinfunction "\\CS_19") (pintype "input"))
      (node (ref "U4") (pin "1") (pinfunction "IO_L83N_VREF_3_1") (pintype "bidirectional"))
    )
    (net (code "44") (name "/RAM_DQ0") (class "Default")
      (node (ref "IC2") (pin "2") (pinfunction "DQ0_2") (pintype "tri_state"))
      (node (ref "U4") (pin "9") (pinfunction "IO_L50N_3_9") (pintype "bidirectional"))
    )
    (net (code "45") (name "/RAM_DQ1") (class "Default")
      (node (ref "IC2") (pin "4") (pinfunction "DQ1_4") (pintype "tri_state"))
      (node (ref "U4") (pin "10") (pinfunction "IO_L50P_3_10") (pintype "bidirectional"))
    )
    (net (code "46") (name "/RAM_DQ2") (class "Default")
      (node (ref "IC2") (pin "5") (pinfunction "DQ2_5") (pintype "tri_state"))
      (node (ref "U4") (pin "11") (pinfunction "IO_L49N_3_11") (pintype "bidirectional"))
    )
    (net (code "47") (name "/RAM_DQ3") (class "Default")
      (node (ref "IC2") (pin "7") (pinfunction "DQ3_7") (pintype "tri_state"))
      (node (ref "U4") (pin "12") (pinfunction "IO_L49P_3_12") (pintype "bidirectional"))
    )
    (net (code "48") (name "/RAM_DQ4") (class "Default")
      (node (ref "IC2") (pin "8") (pinfunction "DQ4_8") (pintype "tri_state"))
      (node (ref "U4") (pin "14") (pinfunction "IO_L44N_GCLK20_3_14") (pintype "bidirectional"))
    )
    (net (code "49") (name "/RAM_DQ5") (class "Default")
      (node (ref "IC2") (pin "10") (pinfunction "DQ5_10") (pintype "tri_state"))
      (node (ref "U4") (pin "15") (pinfunction "IO_L44P_GCLK21_3_15") (pintype "bidirectional"))
    )
    (net (code "50") (name "/RAM_DQ6") (class "Default")
      (node (ref "IC2") (pin "11") (pinfunction "DQ6_11") (pintype "tri_state"))
      (node (ref "U4") (pin "16") (pinfunction "IO_L43N_GCLK22_IRDY2_3_16") (pintype "bidirectional"))
    )
    (net (code "51") (name "/RAM_DQ7") (class "Default")
      (node (ref "IC2") (pin "13") (pinfunction "DQ7_13") (pintype "tri_state"))
      (node (ref "U4") (pin "8") (pinfunction "IO_L51P_3_8") (pintype "bidirectional"))
    )
    (net (code "52") (name "/RAM_DQ8") (class "Default")
      (node (ref "IC2") (pin "42") (pinfunction "DQ8_42") (pintype "tri_state"))
      (node (ref "U4") (pin "21") (pinfunction "IO_L42N_GCLK24_3_21") (pintype "bidirectional"))
    )
    (net (code "53") (name "/RAM_DQ9") (class "Default")
      (node (ref "IC2") (pin "44") (pinfunction "DQ9_44") (pintype "tri_state"))
      (node (ref "U4") (pin "22") (pinfunction "IO_L42P_GCLK25_TRDY2_3_22") (pintype "bidirectional"))
    )
    (net (code "54") (name "/RAM_DQ10") (class "Default")
      (node (ref "IC2") (pin "45") (pinfunction "DQ10_45") (pintype "tri_state"))
      (node (ref "U4") (pin "23") (pinfunction "IO_L41N_GCLK26_3_23") (pintype "bidirectional"))
    )
    (net (code "55") (name "/RAM_DQ11") (class "Default")
      (node (ref "IC2") (pin "47") (pinfunction "DQ11_47") (pintype "tri_state"))
      (node (ref "U4") (pin "24") (pinfunction "IO_L41P_GCLK27_3_24") (pintype "bidirectional"))
    )
    (net (code "56") (name "/RAM_DQ12") (class "Default")
      (node (ref "IC2") (pin "48") (pinfunction "DQ12_48") (pintype "tri_state"))
      (node (ref "U4") (pin "26") (pinfunction "IO_L37N_3_26") (pintype "bidirectional"))
    )
    (net (code "57") (name "/RAM_DQ13") (class "Default")
      (node (ref "IC2") (pin "50") (pinfunction "DQ13_50") (pintype "tri_state"))
      (node (ref "U4") (pin "27") (pinfunction "IO_L37P_3_27") (pintype "bidirectional"))
    )
    (net (code "58") (name "/RAM_DQ14") (class "Default")
      (node (ref "IC2") (pin "51") (pinfunction "DQ14_51") (pintype "tri_state"))
      (node (ref "U4") (pin "29") (pinfunction "IO_L36N_3_29") (pintype "bidirectional"))
    )
    (net (code "59") (name "/RAM_DQ15") (class "Default")
      (node (ref "IC2") (pin "53") (pinfunction "DQ15_53") (pintype "tri_state"))
      (node (ref "U4") (pin "30") (pinfunction "IO_L36P_3_30") (pintype "bidirectional"))
    )
    (net (code "60") (name "/RAM_DQMH") (class "Default")
      (node (ref "IC2") (pin "39") (pinfunction "DQMH_39") (pintype "input"))
      (node (ref "U4") (pin "17") (pinfunction "IO_L43P_GCLK23_3_17") (pintype "bidirectional"))
    )
    (net (code "61") (name "/RAM_DQML") (class "Default")
      (node (ref "IC2") (pin "15") (pinfunction "DQML_15") (pintype "input"))
      (node (ref "U4") (pin "7") (pinfunction "IO_L51N_3_7") (pintype "bidirectional"))
    )
    (net (code "62") (name "/RESET") (class "Default")
      (node (ref "R14") (pin "1") (pinfunction "P$1_1") (pintype "passive"))
      (node (ref "U4") (pin "37") (pinfunction "PROGRAM_B_2_37") (pintype "input"))
    )
    (net (code "63") (name "/TCK") (class "Default")
      (node (ref "IC1") (pin "38") (pinfunction "BDBUS0_38") (pintype "bidirectional"))
      (node (ref "U4") (pin "109") (pinfunction "TCK_109") (pintype "input"))
    )
    (net (code "64") (name "/TDI") (class "Default")
      (node (ref "IC1") (pin "39") (pinfunction "BDBUS1_39") (pintype "bidirectional"))
      (node (ref "U4") (pin "110") (pinfunction "TDI_110") (pintype "input"))
    )
    (net (code "65") (name "/TDO") (class "Default")
      (node (ref "IC1") (pin "40") (pinfunction "BDBUS2_40") (pintype "bidirectional"))
      (node (ref "U4") (pin "106") (pinfunction "TDO_106") (pintype "output"))
    )
    (net (code "66") (name "/TMS") (class "Default")
      (node (ref "IC1") (pin "41") (pinfunction "BDBUS3_41") (pintype "bidirectional"))
      (node (ref "U4") (pin "107") (pinfunction "TMS_107") (pintype "input"))
    )
    (net (code "67") (name "/USB_CLKOUT") (class "Default")
      (node (ref "IC1") (pin "32") (pinfunction "ACBUS5_32") (pintype "bidirectional"))
      (node (ref "U4") (pin "123") (pinfunction "IO_L37N_GCLK12_0_123") (pintype "bidirectional"))
    )
    (net (code "68") (name "/USB_D0") (class "Default")
      (node (ref "IC1") (pin "16") (pinfunction "ADBUS0_16") (pintype "bidirectional"))
      (node (ref "U4") (pin "127") (pinfunction "IO_L36P_GCLK15_0_127") (pintype "bidirectional"))
    )
    (net (code "69") (name "/USB_D1") (class "Default")
      (node (ref "IC1") (pin "17") (pinfunction "ADBUS1_17") (pintype "bidirectional"))
      (node (ref "U4") (pin "126") (pinfunction "IO_L36N_GCLK14_0_126") (pintype "bidirectional"))
    )
    (net (code "70") (name "/USB_D2") (class "Default")
      (node (ref "IC1") (pin "18") (pinfunction "ADBUS2_18") (pintype "bidirectional"))
      (node (ref "U4") (pin "124") (pinfunction "IO_L37P_GCLK13_0_124") (pintype "bidirectional"))
    )
    (net (code "71") (name "/USB_D3") (class "Default")
      (node (ref "IC1") (pin "19") (pinfunction "ADBUS3_19") (pintype "bidirectional"))
      (node (ref "U4") (pin "121") (pinfunction "IO_L62P_0_121") (pintype "bidirectional"))
    )
    (net (code "72") (name "/USB_D4") (class "Default")
      (node (ref "IC1") (pin "21") (pinfunction "ADBUS4_21") (pintype "bidirectional"))
      (node (ref "U4") (pin "120") (pinfunction "IO_L62N_VREF_0_120") (pintype "bidirectional"))
    )
    (net (code "73") (name "/USB_D5") (class "Default")
      (node (ref "IC1") (pin "22") (pinfunction "ADBUS5_22") (pintype "bidirectional"))
      (node (ref "U4") (pin "119") (pinfunction "IO_L63P_SCP7_0_119") (pintype "bidirectional"))
    )
    (net (code "74") (name "/USB_D6") (class "Default")
      (node (ref "IC1") (pin "23") (pinfunction "ADBUS6_23") (pintype "bidirectional"))
      (node (ref "U4") (pin "118") (pinfunction "IO_L63N_SCP6_0_118") (pintype "bidirectional"))
    )
    (net (code "75") (name "/USB_D7") (class "Default")
      (node (ref "IC1") (pin "24") (pinfunction "ADBUS7_24") (pintype "bidirectional"))
      (node (ref "U4") (pin "117") (pinfunction "IO_L64P_SCP5_0_117") (pintype "bidirectional"))
    )
    (net (code "76") (name "/USB_DM") (class "Default")
      (node (ref "IC1") (pin "7") (pinfunction "D-_7") (pintype "bidirectional"))
      (node (ref "USB1") (pin "2") (pinfunction "D-_2") (pintype "input"))
    )
    (net (code "77") (name "/USB_DP") (class "Default")
      (node (ref "IC1") (pin "8") (pinfunction "D+_8") (pintype "bidirectional"))
      (node (ref "USB1") (pin "3") (pinfunction "D+_3") (pintype "input"))
    )
    (net (code "78") (name "/USB_GND") (class "Default")
      (node (ref "R3") (pin "1") (pinfunction "P$1_1") (pintype "passive"))
      (node (ref "R9") (pin "2") (pinfunction "P$2_2") (pintype "passive"))
      (node (ref "USB1") (pin "5") (pinfunction "GND_5") (pintype "input"))
    )
    (net (code "79") (name "/USB_V") (class "Default")
      (node (ref "R1") (pin "1") (pinfunction "P$1_1") (pintype "passive"))
      (node (ref "USB1") (pin "1") (pinfunction "V_BUS_1") (pintype "input"))
    )
    (net (code "80") (name "/~{DAC1_CS}") (class "Default")
      (node (ref "U4") (pin "50") (pinfunction "IO_L31N_GCLK30_D15_2_50") (pintype "bidirectional"))
      (node (ref "U9") (pin "11") (pinfunction "~{CS}_11") (pintype "input"))
    )
    (net (code "81") (name "/~{DAC1_LDAC}") (class "Default")
      (node (ref "U4") (pin "48") (pinfunction "IO_L48P_D7_2_48") (pintype "bidirectional"))
      (node (ref "U9") (pin "15") (pinfunction "~{LDAC}_15") (pintype "input"))
    )
    (net (code "82") (name "/~{DAC2_CS}") (class "Default")
      (node (ref "U12") (pin "11") (pinfunction "~{CS}_11") (pintype "input"))
      (node (ref "U4") (pin "57") (pinfunction "IO_L14N_D12_2_57") (pintype "bidirectional"))
    )
    (net (code "83") (name "/~{DAC2_LDAC}") (class "Default")
      (node (ref "U12") (pin "15") (pinfunction "~{LDAC}_15") (pintype "input"))
      (node (ref "U4") (pin "56") (pinfunction "IO_L30P_GCLK1_D13_2_56") (pintype "bidirectional"))
    )
    (net (code "84") (name "/~{DAC3_CS}") (class "Default")
      (node (ref "U15") (pin "11") (pinfunction "~{CS}_11") (pintype "input"))
      (node (ref "U4") (pin "80") (pinfunction "IO_L46N_1_80") (pintype "bidirectional"))
    )
    (net (code "85") (name "/~{DAC3_LDAC}") (class "Default")
      (node (ref "U15") (pin "15") (pinfunction "~{LDAC}_15") (pintype "input"))
      (node (ref "U4") (pin "79") (pinfunction "IO_L47P_1_79") (pintype "bidirectional"))
    )
    (net (code "86") (name "/~{DACX_RS}") (class "Default")
      (node (ref "R15") (pin "1") (pinfunction "P$1_1") (pintype "passive"))
      (node (ref "U12") (pin "10") (pinfunction "~{RS}_10") (pintype "input"))
      (node (ref "U15") (pin "10") (pinfunction "~{RS}_10") (pintype "input"))
      (node (ref "U4") (pin "67") (pinfunction "IO_L2P_CMPCLK_2_67") (pintype "bidirectional"))
      (node (ref "U9") (pin "10") (pinfunction "~{RS}_10") (pintype "input"))
    )
    (net (code "87") (name "/~{RAM_CAS}") (class "Default")
      (node (ref "IC2") (pin "17") (pinfunction "~{CAS}_17") (pintype "input"))
      (node (ref "U4") (pin "5") (pinfunction "IO_L52N_3_5") (pintype "bidirectional"))
    )
    (net (code "88") (name "/~{RAM_RAS}") (class "Default")
      (node (ref "IC2") (pin "18") (pinfunction "~{RAS}_18") (pintype "input"))
      (node (ref "U4") (pin "2") (pinfunction "IO_L83P_3_2") (pintype "bidirectional"))
    )
    (net (code "89") (name "/~{RAM_WE}") (class "Default")
      (node (ref "IC2") (pin "16") (pinfunction "~{WE}_16") (pintype "input"))
      (node (ref "U4") (pin "6") (pinfunction "IO_L52P_3_6") (pintype "bidirectional"))
    )
    (net (code "90") (name "/~{USB_OE}") (class "Default")
      (node (ref "IC1") (pin "33") (pinfunction "ACBUS6_33") (pintype "bidirectional"))
      (node (ref "U4") (pin "111") (pinfunction "IO_L66N_SCP0_0_111") (pintype "bidirectional"))
    )
    (net (code "91") (name "/~{USB_RD}") (class "Default")
      (node (ref "IC1") (pin "28") (pinfunction "ACBUS2_28") (pintype "bidirectional"))
      (node (ref "U4") (pin "114") (pinfunction "IO_L65N_SCP2_0_114") (pintype "bidirectional"))
    )
    (net (code "92") (name "/~{USB_RESET}") (class "Default")
      (node (ref "IC1") (pin "14") (pinfunction "-RESET_14") (pintype "input"))
      (node (ref "R6") (pin "1") (pinfunction "P$1_1") (pintype "passive"))
      (node (ref "R7") (pin "1") (pinfunction "P$1_1") (pintype "passive"))
    )
    (net (code "93") (name "/~{USB_RXF}") (class "Default")
      (node (ref "IC1") (pin "26") (pinfunction "ACBUS0_26") (pintype "bidirectional"))
      (node (ref "U4") (pin "116") (pinfunction "IO_L64N_SCP4_0_116") (pintype "bidirectional"))
    )
    (net (code "94") (name "/~{USB_TXE}") (class "Default")
      (node (ref "IC1") (pin "27") (pinfunction "ACBUS1_27") (pintype "bidirectional"))
      (node (ref "U4") (pin "115") (pinfunction "IO_L65P_SCP3_0_115") (pintype "bidirectional"))
    )
    (net (code "95") (name "/~{USB_WR}") (class "Default")
      (node (ref "IC1") (pin "29") (pinfunction "ACBUS3_29") (pintype "bidirectional"))
      (node (ref "U4") (pin "112") (pinfunction "IO_L66P_SCP1_0_112") (pintype "bidirectional"))
    )
    (net (code "96") (name "1V2") (class "Default")
      (node (ref "C12") (pin "1") (pinfunction "P$1_1") (pintype "passive"))
      (node (ref "C13") (pin "1") (pinfunction "P$1_1") (pintype "passive"))
      (node (ref "C52") (pin "1") (pinfunction "P$1_1") (pintype "passive"))
      (node (ref "C53") (pin "1") (pinfunction "P$1_1") (pintype "passive"))
      (node (ref "C54") (pin "1") (pinfunction "P$1_1") (pintype "passive"))
      (node (ref "C55") (pin "1") (pinfunction "P$1_1") (pintype "passive"))
      (node (ref "L2") (pin "2") (pinfunction "2_2") (pintype "passive"))
      (node (ref "U2") (pin "4") (pinfunction "FB_4") (pintype "passive"))
      (node (ref "U4") (pin "128") (pinfunction "VCCINT_128") (pintype "input"))
      (node (ref "U4") (pin "19") (pinfunction "VCCINT_19") (pintype "input"))
      (node (ref "U4") (pin "28") (pinfunction "VCCINT_28") (pintype "input"))
      (node (ref "U4") (pin "52") (pinfunction "VCCINT_52") (pintype "input"))
      (node (ref "U4") (pin "89") (pinfunction "VCCINT_89") (pintype "input"))
    )
    (net (code "97") (name "1V8") (class "Default")
      (node (ref "C23") (pin "1") (pinfunction "P$1_1") (pintype "passive"))
      (node (ref "C24") (pin "1") (pinfunction "P$1_1") (pintype "passive"))
      (node (ref "C25") (pin "1") (pinfunction "P$1_1") (pintype "passive"))
      (node (ref "C31") (pin "1") (pinfunction "P$1_1") (pintype "passive"))
      (node (ref "IC1") (pin "12") (pinfunction "VCORE_12") (pintype "power_in"))
      (node (ref "IC1") (pin "37") (pinfunction "VCORE_37") (pintype "power_in"))
      (node (ref "IC1") (pin "49") (pinfunction "VREGOUT_49") (pintype "output"))
      (node (ref "IC1") (pin "64") (pinfunction "VCORE_64") (pintype "power_in"))
    )
    (net (code "98") (name "3V3") (class "Default")
      (node (ref "C26") (pin "1") (pinfunction "P$1_1") (pintype "passive"))
      (node (ref "C27") (pin "1") (pinfunction "P$1_1") (pintype "passive"))
      (node (ref "C28") (pin "1") (pinfunction "P$1_1") (pintype "passive"))
      (node (ref "C29") (pin "1") (pinfunction "P$1_1") (pintype "passive"))
      (node (ref "C3") (pin "1") (pinfunction "P$1_1") (pintype "passive"))
      (node (ref "C30") (pin "1") (pinfunction "P$1_1") (pintype "passive"))
      (node (ref "C34") (pin "1") (pinfunction "P$1_1") (pintype "passive"))
      (node (ref "C35") (pin "1") (pinfunction "P$1_1") (pintype "passive"))
      (node (ref "C36") (pin "1") (pinfunction "P$1_1") (pintype "passive"))
      (node (ref "C37") (pin "1") (pinfunction "P$1_1") (pintype "passive"))
      (node (ref "C38") (pin "1") (pinfunction "P$1_1") (pintype "passive"))
      (node (ref "C39") (pin "1") (pinfunction "P$1_1") (pintype "passive"))
      (node (ref "C4") (pin "1") (pinfunction "P$1_1") (pintype "passive"))
      (node (ref "C40") (pin "1") (pinfunction "P$1_1") (pintype "passive"))
      (node (ref "C41") (pin "1") (pinfunction "P$1_1") (pintype "passive"))
      (node (ref "C42") (pin "1") (pinfunction "P$1_1") (pintype "passive"))
      (node (ref "C43") (pin "1") (pinfunction "P$1_1") (pintype "passive"))
      (node (ref "C44") (pin "1") (pinfunction "P$1_1") (pintype "passive"))
      (node (ref "C45") (pin "1") (pinfunction "P$1_1") (pintype "passive"))
      (node (ref "C46") (pin "1") (pinfunction "P$1_1") (pintype "passive"))
      (node (ref "C47") (pin "1") (pinfunction "P$1_1") (pintype "passive"))
      (node (ref "C48") (pin "1") (pinfunction "P$1_1") (pintype "passive"))
      (node (ref "C49") (pin "1") (pinfunction "P$1_1") (pintype "passive"))
      (node (ref "C50") (pin "1") (pinfunction "P$1_1") (pintype "passive"))
      (node (ref "C51") (pin "1") (pinfunction "P$1_1") (pintype "passive"))
      (node (ref "C56") (pin "1") (pinfunction "P$1_1") (pintype "passive"))
      (node (ref "C57") (pin "1") (pinfunction "P$1_1") (pintype "passive"))
      (node (ref "C58") (pin "1") (pinfunction "P$1_1") (pintype "passive"))
      (node (ref "C59") (pin "1") (pinfunction "P$1_1") (pintype "passive"))
      (node (ref "C60") (pin "1") (pinfunction "P$1_1") (pintype "passive"))
      (node (ref "C61") (pin "1") (pinfunction "P$1_1") (pintype "passive"))
      (node (ref "C62") (pin "1") (pinfunction "P$1_1") (pintype "passive"))
      (node (ref "C63") (pin "1") (pinfunction "P$1_1") (pintype "passive"))
      (node (ref "C64") (pin "1") (pinfunction "P$1_1") (pintype "passive"))
      (node (ref "IC1") (pin "20") (pinfunction "VCCIO_20") (pintype "power_in"))
      (node (ref "IC1") (pin "30") (pinfunction "ACBUS4_30") (pintype "bidirectional"))
      (node (ref "IC1") (pin "31") (pinfunction "VCCIO_31") (pintype "power_in"))
      (node (ref "IC1") (pin "42") (pinfunction "VCCIO_42") (pintype "power_in"))
      (node (ref "IC1") (pin "50") (pinfunction "VREGIN_50") (pintype "input"))
      (node (ref "IC1") (pin "56") (pinfunction "VCCIO_56") (pintype "power_in"))
      (node (ref "IC2") (pin "1") (pinfunction "VDD_1") (pintype "power_in"))
      (node (ref "IC2") (pin "14") (pinfunction "VDD_14") (pintype "power_in"))
      (node (ref "IC2") (pin "27") (pinfunction "VDD_27") (pintype "power_in"))
      (node (ref "IC2") (pin "3") (pinfunction "VDDQ_3") (pintype "power_in"))
      (node (ref "IC2") (pin "43") (pinfunction "VDDQ_43") (pintype "power_in"))
      (node (ref "IC2") (pin "49") (pinfunction "VDDQ_49") (pintype "power_in"))
      (node (ref "IC2") (pin "9") (pinfunction "VDDQ_9") (pintype "power_in"))
      (node (ref "L1") (pin "2") (pinfunction "2_2") (pintype "passive"))
      (node (ref "Q4") (pin "1") (pinfunction "OE_1") (pintype "input"))
      (node (ref "Q4") (pin "4") (pinfunction "VCC_4") (pintype "power_in"))
      (node (ref "R10") (pin "2") (pinfunction "P$2_2") (pintype "passive"))
      (node (ref "R11") (pin "2") (pinfunction "P$2_2") (pintype "passive"))
      (node (ref "R12") (pin "2") (pinfunction "P$2_2") (pintype "passive"))
      (node (ref "R14") (pin "2") (pinfunction "P$2_2") (pintype "passive"))
      (node (ref "R4") (pin "1") (pinfunction "P$1_1") (pintype "passive"))
      (node (ref "R5") (pin "1") (pinfunction "P$1_1") (pintype "passive"))
      (node (ref "R6") (pin "2") (pinfunction "P$2_2") (pintype "passive"))
      (node (ref "SV2") (pin "10") (pinfunction "10_10") (pintype "passive"))
      (node (ref "U1") (pin "4") (pinfunction "FB_4") (pintype "passive"))
      (node (ref "U2") (pin "3") (pinfunction "EN_3") (pintype "passive"))
      (node (ref "U3") (pin "6") (pinfunction "VCC_6") (pintype "power_in"))
      (node (ref "U4") (pin "103") (pinfunction "VCCO_1_103") (pintype "input"))
      (node (ref "U4") (pin "122") (pinfunction "VCCO_0_122") (pintype "input"))
      (node (ref "U4") (pin "125") (pinfunction "VCCO_0_125") (pintype "input"))
      (node (ref "U4") (pin "129") (pinfunction "VCCAUX_129") (pintype "input"))
      (node (ref "U4") (pin "135") (pinfunction "VCCO_0_135") (pintype "input"))
      (node (ref "U4") (pin "18") (pinfunction "VCCO_3_18") (pintype "input"))
      (node (ref "U4") (pin "20") (pinfunction "VCCAUX_20") (pintype "input"))
      (node (ref "U4") (pin "31") (pinfunction "VCCO_3_31") (pintype "input"))
      (node (ref "U4") (pin "36") (pinfunction "VCCAUX_36") (pintype "input"))
      (node (ref "U4") (pin "4") (pinfunction "VCCO_3_4") (pintype "input"))
      (node (ref "U4") (pin "42") (pinfunction "VCCO_2_42") (pintype "input"))
      (node (ref "U4") (pin "53") (pinfunction "VCCAUX_53") (pintype "input"))
      (node (ref "U4") (pin "63") (pinfunction "VCCO_2_63") (pintype "input"))
      (node (ref "U4") (pin "69") (pinfunction "IO_L1N_M0_CMPMISO_2_69") (pintype "bidirectional"))
      (node (ref "U4") (pin "76") (pinfunction "VCCO_1_76") (pintype "input"))
      (node (ref "U4") (pin "86") (pinfunction "VCCO_1_86") (pintype "input"))
      (node (ref "U4") (pin "90") (pinfunction "VCCAUX_90") (pintype "input"))
      (node (ref "U5") (pin "3") (pinfunction "~{WP}_3") (pintype "input"))
      (node (ref "U5") (pin "7") (pinfunction "~{RESET}_7") (pintype "input"))
      (node (ref "U5") (pin "8") (pinfunction "VCC_8") (pintype "power_in"))
    )
    (net (code "99") (name "5V0") (class "Default")
      (node (ref "C1") (pin "1") (pinfunction "P$1_1") (pintype "passive"))
      (node (ref "C10") (pin "1") (pinfunction "P$1_1") (pintype "passive"))
      (node (ref "C11") (pin "1") (pinfunction "P$1_1") (pintype "passive"))
      (node (ref "C2") (pin "1") (pinfunction "P$1_1") (pintype "passive"))
      (node (ref "R1") (pin "2") (pinfunction "P$2_2") (pintype "passive"))
      (node (ref "U1") (pin "1") (pinfunction "VIN_1") (pintype "input"))
      (node (ref "U1") (pin "3") (pinfunction "EN_3") (pintype "passive"))
      (node (ref "U2") (pin "1") (pinfunction "VIN_1") (pintype "input"))
    )
    (net (code "100") (name "A+3V3") (class "Default")
      (node (ref "C73") (pin "1") (pinfunction "P$1_1") (pintype "passive"))
      (node (ref "C82") (pin "1") (pinfunction "P$1_1") (pintype "passive"))
      (node (ref "C91") (pin "1") (pinfunction "P$1_1") (pintype "passive"))
      (node (ref "C92") (pin "1") (pinfunction "P$1_1") (pintype "passive"))
      (node (ref "C93") (pin "1") (pinfunction "P$1_1") (pintype "passive"))
      (node (ref "C94") (pin "1") (pinfunction "P$1_1") (pintype "passive"))
      (node (ref "C95") (pin "+") (pinfunction "+_+") (pintype "passive"))
      (node (ref "U12") (pin "13") (pinfunction "VDD_13") (pintype "power_in"))
      (node (ref "U12") (pin "14") (pinfunction "MSB_14") (pintype "input"))
      (node (ref "U15") (pin "13") (pinfunction "VDD_13") (pintype "power_in"))
      (node (ref "U15") (pin "14") (pinfunction "MSB_14") (pintype "input"))
      (node (ref "U16") (pin "1") (pinfunction "OUT_1") (pintype "output"))
      (node (ref "U16") (pin "4") (pinfunction "-IN_4") (pintype "input"))
      (node (ref "U9") (pin "13") (pinfunction "VDD_13") (pintype "power_in"))
      (node (ref "U9") (pin "14") (pinfunction "MSB_14") (pintype "input"))
    )
    (net (code "101") (name "A+12V") (class "Default")
      (node (ref "C100") (pin "1") (pinfunction "P$1_1") (pintype "passive"))
      (node (ref "C102") (pin "1") (pinfunction "P$1_1") (pintype "passive"))
      (node (ref "C6") (pin "1") (pinfunction "P$1_1") (pintype "passive"))
      (node (ref "C65") (pin "1") (pinfunction "P$1_1") (pintype "passive"))
      (node (ref "C67") (pin "1") (pinfunction "P$1_1") (pintype "passive"))
      (node (ref "C69") (pin "1") (pinfunction "P$1_1") (pintype "passive"))
      (node (ref "C7") (pin "1") (pinfunction "P$1_1") (pintype "passive"))
      (node (ref "C74") (pin "1") (pinfunction "P$1_1") (pintype "passive"))
      (node (ref "C76") (pin "1") (pinfunction "P$1_1") (pintype "passive"))
      (node (ref "C78") (pin "1") (pinfunction "P$1_1") (pintype "passive"))
      (node (ref "C8") (pin "1") (pinfunction "P$1_1") (pintype "passive"))
      (node (ref "C83") (pin "1") (pinfunction "P$1_1") (pintype "passive"))
      (node (ref "C85") (pin "1") (pinfunction "P$1_1") (pintype "passive"))
      (node (ref "C87") (pin "1") (pinfunction "P$1_1") (pintype "passive"))
      (node (ref "C9") (pin "+") (pinfunction "+_+") (pintype "passive"))
      (node (ref "C96") (pin "1") (pinfunction "P$1_1") (pintype "passive"))
      (node (ref "C97") (pin "1") (pinfunction "P$1_1") (pintype "passive"))
      (node (ref "C98") (pin "1") (pinfunction "P$1_1") (pintype "passive"))
      (node (ref "Q1") (pin "3") (pinfunction "OUT_3") (pintype "output"))
      (node (ref "R16") (pin "1") (pinfunction "P$1_1") (pintype "passive"))
      (node (ref "U10") (pin "2") (pinfunction "V+_2") (pintype "power_in"))
      (node (ref "U11") (pin "4") (pinfunction "V+_4") (pintype "power_in"))
      (node (ref "U13") (pin "2") (pinfunction "V+_2") (pintype "power_in"))
      (node (ref "U14") (pin "4") (pinfunction "V+_4") (pintype "power_in"))
      (node (ref "U16") (pin "5") (pinfunction "V+_5") (pintype "power_in"))
      (node (ref "U7") (pin "2") (pinfunction "V+_2") (pintype "power_in"))
      (node (ref "U8") (pin "4") (pinfunction "V+_4") (pintype "power_in"))
    )
    (net (code "102") (name "A-12V") (class "Default")
      (node (ref "C101") (pin "2") (pinfunction "P$2_2") (pintype "passive"))
      (node (ref "C103") (pin "2") (pinfunction "P$2_2") (pintype "passive"))
      (node (ref "C14") (pin "2") (pinfunction "P$2_2") (pintype "passive"))
      (node (ref "C15") (pin "2") (pinfunction "P$2_2") (pintype "passive"))
      (node (ref "C16") (pin "2") (pinfunction "P$2_2") (pintype "passive"))
      (node (ref "C17") (pin "-") (pinfunction "-_-") (pintype "passive"))
      (node (ref "C68") (pin "2") (pinfunction "P$2_2") (pintype "passive"))
      (node (ref "C70") (pin "2") (pinfunction "P$2_2") (pintype "passive"))
      (node (ref "C77") (pin "2") (pinfunction "P$2_2") (pintype "passive"))
      (node (ref "C79") (pin "2") (pinfunction "P$2_2") (pintype "passive"))
      (node (ref "C86") (pin "2") (pinfunction "P$2_2") (pintype "passive"))
      (node (ref "C88") (pin "2") (pinfunction "P$2_2") (pintype "passive"))
      (node (ref "C99") (pin "2") (pinfunction "P$2_2") (pintype "passive"))
      (node (ref "Q2") (pin "3") (pinfunction "OUTPUT_3") (pintype "output"))
      (node (ref "U11") (pin "11") (pinfunction "V-_11") (pintype "power_in"))
      (node (ref "U14") (pin "11") (pinfunction "V-_11") (pintype "power_in"))
      (node (ref "U8") (pin "11") (pinfunction "V-_11") (pintype "power_in"))
    )
    (net (code "103") (name "AGND") (class "Default")
      (node (ref "AO1") (pin "2") (pinfunction "2_2") (pintype "passive"))
      (node (ref "AO1") (pin "3") (pinfunction "2_3") (pintype "passive"))
      (node (ref "AO1") (pin "4") (pinfunction "2_4") (pintype "passive"))
      (node (ref "AO1") (pin "5") (pinfunction "2_5") (pintype "passive"))
      (node (ref "AO2") (pin "2") (pinfunction "2_2") (pintype "passive"))
      (node (ref "AO2") (pin "3") (pinfunction "2_3") (pintype "passive"))
      (node (ref "AO2") (pin "4") (pinfunction "2_4") (pintype "passive"))
      (node (ref "AO2") (pin "5") (pinfunction "2_5") (pintype "passive"))
      (node (ref "AO3") (pin "2") (pinfunction "2_2") (pintype "passive"))
      (node (ref "AO3") (pin "3") (pinfunction "2_3") (pintype "passive"))
      (node (ref "AO3") (pin "4") (pinfunction "2_4") (pintype "passive"))
      (node (ref "AO3") (pin "5") (pinfunction "2_5") (pintype "passive"))
      (node (ref "AO4") (pin "2") (pinfunction "2_2") (pintype "passive"))
      (node (ref "AO4") (pin "3") (pinfunction "2_3") (pintype "passive"))
      (node (ref "AO4") (pin "4") (pinfunction "2_4") (pintype "passive"))
      (node (ref "AO4") (pin "5") (pinfunction "2_5") (pintype "passive"))
      (node (ref "AO5") (pin "2") (pinfunction "2_2") (pintype "passive"))
      (node (ref "AO5") (pin "3") (pinfunction "2_3") (pintype "passive"))
      (node (ref "AO5") (pin "4") (pinfunction "2_4") (pintype "passive"))
      (node (ref "AO5") (pin "5") (pinfunction "2_5") (pintype "passive"))
      (node (ref "AO6") (pin "2") (pinfunction "2_2") (pintype "passive"))
      (node (ref "AO6") (pin "3") (pinfunction "2_3") (pintype "passive"))
      (node (ref "AO6") (pin "4") (pinfunction "2_4") (pintype "passive"))
      (node (ref "AO6") (pin "5") (pinfunction "2_5") (pintype "passive"))
      (node (ref "C100") (pin "2") (pinfunction "P$2_2") (pintype "passive"))
      (node (ref "C101") (pin "1") (pinfunction "P$1_1") (pintype "passive"))
      (node (ref "C102") (pin "2") (pinfunction "P$2_2") (pintype "passive"))
      (node (ref "C103") (pin "1") (pinfunction "P$1_1") (pintype "passive"))
      (node (ref "C14") (pin "1") (pinfunction "P$1_1") (pintype "passive"))
      (node (ref "C15") (pin "1") (pinfunction "P$1_1") (pintype "passive"))
      (node (ref "C16") (pin "1") (pinfunction "P$1_1") (pintype "passive"))
      (node (ref "C17") (pin "+") (pinfunction "+_+") (pintype "passive"))
      (node (ref "C18") (pin "2") (pinfunction "P$2_2") (pintype "passive"))
      (node (ref "C5") (pin "2") (pinfunction "P$2_2") (pintype "passive"))
      (node (ref "C6") (pin "2") (pinfunction "P$2_2") (pintype "passive"))
      (node (ref "C65") (pin "2") (pinfunction "P$2_2") (pintype "passive"))
      (node (ref "C66") (pin "2") (pinfunction "P$2_2") (pintype "passive"))
      (node (ref "C67") (pin "2") (pinfunction "P$2_2") (pintype "passive"))
      (node (ref "C68") (pin "1") (pinfunction "P$1_1") (pintype "passive"))
      (node (ref "C69") (pin "2") (pinfunction "P$2_2") (pintype "passive"))
      (node (ref "C7") (pin "2") (pinfunction "P$2_2") (pintype "passive"))
      (node (ref "C70") (pin "1") (pinfunction "P$1_1") (pintype "passive"))
      (node (ref "C73") (pin "2") (pinfunction "P$2_2") (pintype "passive"))
      (node (ref "C74") (pin "2") (pinfunction "P$2_2") (pintype "passive"))
      (node (ref "C75") (pin "2") (pinfunction "P$2_2") (pintype "passive"))
      (node (ref "C76") (pin "2") (pinfunction "P$2_2") (pintype "passive"))
      (node (ref "C77") (pin "1") (pinfunction "P$1_1") (pintype "passive"))
      (node (ref "C78") (pin "2") (pinfunction "P$2_2") (pintype "passive"))
      (node (ref "C79") (pin "1") (pinfunction "P$1_1") (pintype "passive"))
      (node (ref "C8") (pin "2") (pinfunction "P$2_2") (pintype "passive"))
      (node (ref "C82") (pin "2") (pinfunction "P$2_2") (pintype "passive"))
      (node (ref "C83") (pin "2") (pinfunction "P$2_2") (pintype "passive"))
      (node (ref "C84") (pin "2") (pinfunction "P$2_2") (pintype "passive"))
      (node (ref "C85") (pin "2") (pinfunction "P$2_2") (pintype "passive"))
      (node (ref "C86") (pin "1") (pinfunction "P$1_1") (pintype "passive"))
      (node (ref "C87") (pin "2") (pinfunction "P$2_2") (pintype "passive"))
      (node (ref "C88") (pin "1") (pinfunction "P$1_1") (pintype "passive"))
      (node (ref "C9") (pin "-") (pinfunction "-_-") (pintype "passive"))
      (node (ref "C91") (pin "2") (pinfunction "P$2_2") (pintype "passive"))
      (node (ref "C92") (pin "2") (pinfunction "P$2_2") (pintype "passive"))
      (node (ref "C93") (pin "2") (pinfunction "P$2_2") (pintype "passive"))
      (node (ref "C94") (pin "2") (pinfunction "P$2_2") (pintype "passive"))
      (node (ref "C95") (pin "-") (pinfunction "-_-") (pintype "passive"))
      (node (ref "C96") (pin "2") (pinfunction "P$2_2") (pintype "passive"))
      (node (ref "C97") (pin "2") (pinfunction "P$2_2") (pintype "passive"))
      (node (ref "C98") (pin "2") (pinfunction "P$2_2") (pintype "passive"))
      (node (ref "C99") (pin "1") (pinfunction "P$1_1") (pintype "passive"))
      (node (ref "P1") (pin "P$3") (pinfunction "3_P$3") (pintype "bidirectional"))
      (node (ref "Q1") (pin "2") (pinfunction "GND_2") (pintype "passive"))
      (node (ref "Q2") (pin "1") (pinfunction "GND_1") (pintype "passive"))
      (node (ref "R15") (pin "2") (pinfunction "P$2_2") (pintype "passive"))
      (node (ref "R17") (pin "2") (pinfunction "P$2_2") (pintype "passive"))
      (node (ref "R2") (pin "1") (pinfunction "P$1_1") (pintype "passive"))
      (node (ref "U10") (pin "4") (pinfunction "COM_4") (pintype "passive"))
      (node (ref "U11") (pin "10") (pinfunction "+IN_C_10") (pintype "input"))
      (node (ref "U11") (pin "12") (pinfunction "+IN_D_12") (pintype "input"))
      (node (ref "U11") (pin "3") (pinfunction "+IN_A_3") (pintype "input"))
      (node (ref "U11") (pin "5") (pinfunction "+IN_B_5") (pintype "input"))
      (node (ref "U12") (pin "12") (pinfunction "DGND_12") (pintype "passive"))
      (node (ref "U12") (pin "4") (pinfunction "AGNDA_4") (pintype "passive"))
      (node (ref "U12") (pin "5") (pinfunction "AGNDB_5") (pintype "passive"))
      (node (ref "U13") (pin "4") (pinfunction "COM_4") (pintype "passive"))
      (node (ref "U14") (pin "10") (pinfunction "+IN_C_10") (pintype "input"))
      (node (ref "U14") (pin "12") (pinfunction "+IN_D_12") (pintype "input"))
      (node (ref "U14") (pin "3") (pinfunction "+IN_A_3") (pintype "input"))
      (node (ref "U14") (pin "5") (pinfunction "+IN_B_5") (pintype "input"))
      (node (ref "U15") (pin "12") (pinfunction "DGND_12") (pintype "passive"))
      (node (ref "U15") (pin "4") (pinfunction "AGNDA_4") (pintype "passive"))
      (node (ref "U15") (pin "5") (pinfunction "AGNDB_5") (pintype "passive"))
      (node (ref "U16") (pin "2") (pinfunction "V-_2") (pintype "power_in"))
      (node (ref "U7") (pin "4") (pinfunction "COM_4") (pintype "passive"))
      (node (ref "U8") (pin "10") (pinfunction "+IN_C_10") (pintype "input"))
      (node (ref "U8") (pin "12") (pinfunction "+IN_D_12") (pintype "input"))
      (node (ref "U8") (pin "3") (pinfunction "+IN_A_3") (pintype "input"))
      (node (ref "U8") (pin "5") (pinfunction "+IN_B_5") (pintype "input"))
      (node (ref "U9") (pin "12") (pinfunction "DGND_12") (pintype "passive"))
      (node (ref "U9") (pin "4") (pinfunction "AGNDA_4") (pintype "passive"))
      (node (ref "U9") (pin "5") (pinfunction "AGNDB_5") (pintype "passive"))
    )
    (net (code "104") (name "GND") (class "Default")
      (node (ref "C1") (pin "2") (pinfunction "P$2_2") (pintype "passive"))
      (node (ref "C10") (pin "2") (pinfunction "P$2_2") (pintype "passive"))
      (node (ref "C11") (pin "2") (pinfunction "P$2_2") (pintype "passive"))
      (node (ref "C12") (pin "2") (pinfunction "P$2_2") (pintype "passive"))
      (node (ref "C13") (pin "2") (pinfunction "P$2_2") (pintype "passive"))
      (node (ref "C19") (pin "2") (pinfunction "P$2_2") (pintype "passive"))
      (node (ref "C2") (pin "2") (pinfunction "P$2_2") (pintype "passive"))
      (node (ref "C20") (pin "2") (pinfunction "P$2_2") (pintype "passive"))
      (node (ref "C21") (pin "2") (pinfunction "P$2_2") (pintype "passive"))
      (node (ref "C22") (pin "2") (pinfunction "P$2_2") (pintype "passive"))
      (node (ref "C23") (pin "2") (pinfunction "P$2_2") (pintype "passive"))
      (node (ref "C24") (pin "2") (pinfunction "P$2_2") (pintype "passive"))
      (node (ref "C25") (pin "2") (pinfunction "P$2_2") (pintype "passive"))
      (node (ref "C26") (pin "2") (pinfunction "P$2_2") (pintype "passive"))
      (node (ref "C27") (pin "2") (pinfunction "P$2_2") (pintype "passive"))
      (node (ref "C28") (pin "2") (pinfunction "P$2_2") (pintype "passive"))
      (node (ref "C29") (pin "2") (pinfunction "P$2_2") (pintype "passive"))
      (node (ref "C3") (pin "2") (pinfunction "P$2_2") (pintype "passive"))
      (node (ref "C30") (pin "2") (pinfunction "P$2_2") (pintype "passive"))
      (node (ref "C31") (pin "2") (pinfunction "P$2_2") (pintype "passive"))
      (node (ref "C32") (pin "2") (pinfunction "P$2_2") (pintype "passive"))
      (node (ref "C33") (pin "2") (pinfunction "P$2_2") (pintype "passive"))
      (node (ref "C34") (pin "2") (pinfunction "P$2_2") (pintype "passive"))
      (node (ref "C35") (pin "2") (pinfunction "P$2_2") (pintype "passive"))
      (node (ref "C36") (pin "2") (pinfunction "P$2_2") (pintype "passive"))
      (node (ref "C37") (pin "2") (pinfunction "P$2_2") (pintype "passive"))
      (node (ref "C38") (pin "2") (pinfunction "P$2_2") (pintype "passive"))
      (node (ref "C39") (pin "2") (pinfunction "P$2_2") (pintype "passive"))
      (node (ref "C4") (pin "2") (pinfunction "P$2_2") (pintype "passive"))
      (node (ref "C40") (pin "2") (pinfunction "P$2_2") (pintype "passive"))
      (node (ref "C41") (pin "2") (pinfunction "P$2_2") (pintype "passive"))
      (node (ref "C42") (pin "2") (pinfunction "P$2_2") (pintype "passive"))
      (node (ref "C43") (pin "2") (pinfunction "P$2_2") (pintype "passive"))
      (node (ref "C44") (pin "2") (pinfunction "P$2_2") (pintype "passive"))
      (node (ref "C45") (pin "2") (pinfunction "P$2_2") (pintype "passive"))
      (node (ref "C46") (pin "2") (pinfunction "P$2_2") (pintype "passive"))
      (node (ref "C47") (pin "2") (pinfunction "P$2_2") (pintype "passive"))
      (node (ref "C48") (pin "2") (pinfunction "P$2_2") (pintype "passive"))
      (node (ref "C49") (pin "2") (pinfunction "P$2_2") (pintype "passive"))
      (node (ref "C50") (pin "2") (pinfunction "P$2_2") (pintype "passive"))
      (node (ref "C51") (pin "2") (pinfunction "P$2_2") (pintype "passive"))
      (node (ref "C52") (pin "2") (pinfunction "P$2_2") (pintype "passive"))
      (node (ref "C53") (pin "2") (pinfunction "P$2_2") (pintype "passive"))
      (node (ref "C54") (pin "2") (pinfunction "P$2_2") (pintype "passive"))
      (node (ref "C55") (pin "2") (pinfunction "P$2_2") (pintype "passive"))
      (node (ref "C56") (pin "2") (pinfunction "P$2_2") (pintype "passive"))
      (node (ref "C57") (pin "2") (pinfunction "P$2_2") (pintype "passive"))
      (node (ref "C58") (pin "2") (pinfunction "P$2_2") (pintype "passive"))
      (node (ref "C59") (pin "2") (pinfunction "P$2_2") (pintype "passive"))
      (node (ref "C60") (pin "2") (pinfunction "P$2_2") (pintype "passive"))
      (node (ref "C61") (pin "2") (pinfunction "P$2_2") (pintype "passive"))
      (node (ref "C62") (pin "2") (pinfunction "P$2_2") (pintype "passive"))
      (node (ref "C63") (pin "2") (pinfunction "P$2_2") (pintype "passive"))
      (node (ref "C64") (pin "2") (pinfunction "P$2_2") (pintype "passive"))
      (node (ref "IC1") (pin "1") (pinfunction "GND_1") (pintype "power_in"))
      (node (ref "IC1") (pin "10") (pinfunction "AGND_10") (pintype "power_in"))
      (node (ref "IC1") (pin "11") (pinfunction "GND_11") (pintype "power_in"))
      (node (ref "IC1") (pin "13") (pinfunction "TEST_13") (pintype "input"))
      (node (ref "IC1") (pin "15") (pinfunction "GND_15") (pintype "power_in"))
      (node (ref "IC1") (pin "25") (pinfunction "GND_25") (pintype "power_in"))
      (node (ref "IC1") (pin "35") (pinfunction "GND_35") (pintype "power_in"))
      (node (ref "IC1") (pin "47") (pinfunction "GND_47") (pintype "power_in"))
      (node (ref "IC1") (pin "5") (pinfunction "GND_5") (pintype "power_in"))
      (node (ref "IC1") (pin "51") (pinfunction "GND_51") (pintype "power_in"))
      (node (ref "IC2") (pin "12") (pinfunction "VSSQ_12") (pintype "power_in"))
      (node (ref "IC2") (pin "28") (pinfunction "VSS_28") (pintype "power_in"))
      (node (ref "IC2") (pin "41") (pinfunction "VSS_41") (pintype "power_in"))
      (node (ref "IC2") (pin "46") (pinfunction "VSSQ_46") (pintype "power_in"))
      (node (ref "IC2") (pin "52") (pinfunction "VSSQ_52") (pintype "power_in"))
      (node (ref "IC2") (pin "54") (pinfunction "VSS_54") (pintype "power_in"))
      (node (ref "IC2") (pin "6") (pinfunction "VSSQ_6") (pintype "power_in"))
      (node (ref "Q4") (pin "2") (pinfunction "GND_2") (pintype "power_in"))
      (node (ref "R2") (pin "2") (pinfunction "P$2_2") (pintype "passive"))
      (node (ref "R3") (pin "2") (pinfunction "P$2_2") (pintype "passive"))
      (node (ref "R7") (pin "2") (pinfunction "P$2_2") (pintype "passive"))
      (node (ref "R8") (pin "2") (pinfunction "P$2_2") (pintype "passive"))
      (node (ref "SV1") (pin "5") (pinfunction "5_5") (pintype "passive"))
      (node (ref "SV1") (pin "6") (pinfunction "6_6") (pintype "passive"))
      (node (ref "SV2") (pin "9") (pinfunction "9_9") (pintype "passive"))
      (node (ref "U1") (pin "2") (pinfunction "GND_2") (pintype "passive"))
      (node (ref "U2") (pin "2") (pinfunction "GND_2") (pintype "passive"))
      (node (ref "U3") (pin "2") (pinfunction "GND_2") (pintype "power_in"))
      (node (ref "U4") (pin "104") (pinfunction "IO_L1N_VREF_1_104") (pintype "bidirectional"))
      (node (ref "U4") (pin "105") (pinfunction "IO_L1P_1_105") (pintype "bidirectional"))
      (node (ref "U4") (pin "108") (pinfunction "GND_108") (pintype "power_in"))
      (node (ref "U4") (pin "113") (pinfunction "GND_113") (pintype "power_in"))
      (node (ref "U4") (pin "13") (pinfunction "GND_13") (pintype "power_in"))
      (node (ref "U4") (pin "130") (pinfunction "GND_130") (pintype "power_in"))
      (node (ref "U4") (pin "136") (pinfunction "GND_136") (pintype "power_in"))
      (node (ref "U4") (pin "144") (pinfunction "IO_L1P_HSWAPEN_0_144") (pintype "bidirectional"))
      (node (ref "U4") (pin "25") (pinfunction "GND_25") (pintype "power_in"))
      (node (ref "U4") (pin "3") (pinfunction "GND_3") (pintype "power_in"))
      (node (ref "U4") (pin "49") (pinfunction "GND_49") (pintype "power_in"))
      (node (ref "U4") (pin "54") (pinfunction "GND_54") (pintype "power_in"))
      (node (ref "U4") (pin "59") (pinfunction "IO_L13N_D10_2_59") (pintype "bidirectional"))
      (node (ref "U4") (pin "60") (pinfunction "IO_L13P_M1_2_60") (pintype "bidirectional"))
      (node (ref "U4") (pin "61") (pinfunction "IO_L12N_D2_MISO3_2_61") (pintype "bidirectional"))
      (node (ref "U4") (pin "62") (pinfunction "IO_L12P_D1_MISO2_2_62") (pintype "bidirectional"))
      (node (ref "U4") (pin "66") (pinfunction "IO_L2N_CMPMOSI_2_66") (pintype "bidirectional"))
      (node (ref "U4") (pin "68") (pinfunction "GND_68") (pintype "power_in"))
      (node (ref "U4") (pin "73") (pinfunction "SUSPEND_73") (pintype "input"))
      (node (ref "U4") (pin "77") (pinfunction "GND_77") (pintype "power_in"))
      (node (ref "U4") (pin "82") (pinfunction "IO_L45N_1_82") (pintype "bidirectional"))
      (node (ref "U4") (pin "83") (pinfunction "IO_L45P_1_83") (pintype "bidirectional"))
      (node (ref "U4") (pin "84") (pinfunction "IO_L43N_GCLK4_1_84") (pintype "bidirectional"))
      (node (ref "U4") (pin "85") (pinfunction "IO_L43P_GCLK5_1_85") (pintype "bidirectional"))
      (node (ref "U4") (pin "91") (pinfunction "GND_91") (pintype "power_in"))
      (node (ref "U4") (pin "94") (pinfunction "IO_L40N_GCLK10_1_94") (pintype "bidirectional"))
      (node (ref "U4") (pin "96") (pinfunction "GND_96") (pintype "power_in"))
      (node (ref "U4") (pin "97") (pinfunction "IO_L34N_1_97") (pintype "bidirectional"))
      (node (ref "U4") (pin "98") (pinfunction "IO_L34P_1_98") (pintype "bidirectional"))
      (node (ref "U5") (pin "4") (pinfunction "GND_4") (pintype "passive"))
    )
    (net (code "105") (name "Net-(C19-P$1)") (class "Default")
      (node (ref "C19") (pin "1") (pinfunction "P$1_1") (pintype "passive"))
      (node (ref "C21") (pin "1") (pinfunction "P$1_1") (pintype "passive"))
      (node (ref "IC1") (pin "4") (pinfunction "VPHY_4") (pintype "power_in"))
      (node (ref "R5") (pin "2") (pinfunction "P$2_2") (pintype "passive"))
    )
    (net (code "106") (name "Net-(C20-P$1)") (class "Default")
      (node (ref "C20") (pin "1") (pinfunction "P$1_1") (pintype "passive"))
      (node (ref "C22") (pin "1") (pinfunction "P$1_1") (pintype "passive"))
      (node (ref "IC1") (pin "9") (pinfunction "VPLL_9") (pintype "power_in"))
      (node (ref "R4") (pin "2") (pinfunction "P$2_2") (pintype "passive"))
    )
    (net (code "107") (name "Net-(C32-P$1)") (class "Default")
      (node (ref "C32") (pin "1") (pinfunction "P$1_1") (pintype "passive"))
      (node (ref "IC1") (pin "2") (pinfunction "XTIN_2") (pintype "input"))
      (node (ref "Q3") (pin "1") (pinfunction "P$1_1") (pintype "passive"))
    )
    (net (code "108") (name "Net-(C33-P$1)") (class "Default")
      (node (ref "C33") (pin "1") (pinfunction "P$1_1") (pintype "passive"))
      (node (ref "IC1") (pin "3") (pinfunction "XTOUT_3") (pintype "output"))
      (node (ref "Q3") (pin "2") (pinfunction "P$2_2") (pintype "passive"))
    )
    (net (code "109") (name "Net-(C66-P$1)") (class "Default")
      (node (ref "C66") (pin "1") (pinfunction "P$1_1") (pintype "passive"))
      (node (ref "U7") (pin "8") (pinfunction "NR_8") (pintype "passive"))
    )
    (net (code "110") (name "Net-(C71-P$1)") (class "Default")
      (node (ref "C71") (pin "1") (pinfunction "P$1_1") (pintype "passive"))
      (node (ref "RN1") (pin "2") (pinfunction "1_2") (pintype "passive"))
      (node (ref "RN1") (pin "3") (pinfunction "1_3") (pintype "passive"))
      (node (ref "U8") (pin "1") (pinfunction "OUT_A_1") (pintype "output"))
      (node (ref "U9") (pin "8") (pinfunction "RFBB_8") (pintype "input"))
    )
    (net (code "111") (name "Net-(C71-P$2)") (class "Default")
      (node (ref "C71") (pin "2") (pinfunction "P$2_2") (pintype "passive"))
      (node (ref "U8") (pin "2") (pinfunction "-IN_A_2") (pintype "input"))
      (node (ref "U9") (pin "6") (pinfunction "IOUTB_6") (pintype "output"))
    )
    (net (code "112") (name "Net-(C72-P$1)") (class "Default")
      (node (ref "C72") (pin "1") (pinfunction "P$1_1") (pintype "passive"))
      (node (ref "RN2") (pin "6") (pinfunction "2_6") (pintype "passive"))
      (node (ref "RN2") (pin "7") (pinfunction "2_7") (pintype "passive"))
      (node (ref "U8") (pin "7") (pinfunction "OUT_B_7") (pintype "output"))
      (node (ref "U9") (pin "1") (pinfunction "RFBA_1") (pintype "input"))
    )
    (net (code "113") (name "Net-(C72-P$2)") (class "Default")
      (node (ref "C72") (pin "2") (pinfunction "P$2_2") (pintype "passive"))
      (node (ref "U8") (pin "6") (pinfunction "-IN_B_6") (pintype "input"))
      (node (ref "U9") (pin "3") (pinfunction "IOUTA_3") (pintype "output"))
    )
    (net (code "114") (name "Net-(C75-P$1)") (class "Default")
      (node (ref "C75") (pin "1") (pinfunction "P$1_1") (pintype "passive"))
      (node (ref "U10") (pin "8") (pinfunction "NR_8") (pintype "passive"))
    )
    (net (code "115") (name "Net-(C80-P$1)") (class "Default")
      (node (ref "C80") (pin "1") (pinfunction "P$1_1") (pintype "passive"))
      (node (ref "RN3") (pin "2") (pinfunction "1_2") (pintype "passive"))
      (node (ref "RN3") (pin "3") (pinfunction "1_3") (pintype "passive"))
      (node (ref "U11") (pin "1") (pinfunction "OUT_A_1") (pintype "output"))
      (node (ref "U12") (pin "8") (pinfunction "RFBB_8") (pintype "input"))
    )
    (net (code "116") (name "Net-(C80-P$2)") (class "Default")
      (node (ref "C80") (pin "2") (pinfunction "P$2_2") (pintype "passive"))
      (node (ref "U11") (pin "2") (pinfunction "-IN_A_2") (pintype "input"))
      (node (ref "U12") (pin "6") (pinfunction "IOUTB_6") (pintype "output"))
    )
    (net (code "117") (name "Net-(C81-P$1)") (class "Default")
      (node (ref "C81") (pin "1") (pinfunction "P$1_1") (pintype "passive"))
      (node (ref "RN4") (pin "6") (pinfunction "2_6") (pintype "passive"))
      (node (ref "RN4") (pin "7") (pinfunction "2_7") (pintype "passive"))
      (node (ref "U11") (pin "7") (pinfunction "OUT_B_7") (pintype "output"))
      (node (ref "U12") (pin "1") (pinfunction "RFBA_1") (pintype "input"))
    )
    (net (code "118") (name "Net-(C81-P$2)") (class "Default")
      (node (ref "C81") (pin "2") (pinfunction "P$2_2") (pintype "passive"))
      (node (ref "U11") (pin "6") (pinfunction "-IN_B_6") (pintype "input"))
      (node (ref "U12") (pin "3") (pinfunction "IOUTA_3") (pintype "output"))
    )
    (net (code "119") (name "Net-(C84-P$1)") (class "Default")
      (node (ref "C84") (pin "1") (pinfunction "P$1_1") (pintype "passive"))
      (node (ref "U13") (pin "8") (pinfunction "NR_8") (pintype "passive"))
    )
    (net (code "120") (name "Net-(C89-P$1)") (class "Default")
      (node (ref "C89") (pin "1") (pinfunction "P$1_1") (pintype "passive"))
      (node (ref "RN5") (pin "2") (pinfunction "1_2") (pintype "passive"))
      (node (ref "RN5") (pin "3") (pinfunction "1_3") (pintype "passive"))
      (node (ref "U14") (pin "1") (pinfunction "OUT_A_1") (pintype "output"))
      (node (ref "U15") (pin "8") (pinfunction "RFBB_8") (pintype "input"))
    )
    (net (code "121") (name "Net-(C89-P$2)") (class "Default")
      (node (ref "C89") (pin "2") (pinfunction "P$2_2") (pintype "passive"))
      (node (ref "U14") (pin "2") (pinfunction "-IN_A_2") (pintype "input"))
      (node (ref "U15") (pin "6") (pinfunction "IOUTB_6") (pintype "output"))
    )
    (net (code "122") (name "Net-(C90-P$1)") (class "Default")
      (node (ref "C90") (pin "1") (pinfunction "P$1_1") (pintype "passive"))
      (node (ref "RN6") (pin "6") (pinfunction "2_6") (pintype "passive"))
      (node (ref "RN6") (pin "7") (pinfunction "2_7") (pintype "passive"))
      (node (ref "U14") (pin "7") (pinfunction "OUT_B_7") (pintype "output"))
      (node (ref "U15") (pin "1") (pinfunction "RFBA_1") (pintype "input"))
    )
    (net (code "123") (name "Net-(C90-P$2)") (class "Default")
      (node (ref "C90") (pin "2") (pinfunction "P$2_2") (pintype "passive"))
      (node (ref "U14") (pin "6") (pinfunction "-IN_B_6") (pintype "input"))
      (node (ref "U15") (pin "3") (pinfunction "IOUTA_3") (pintype "output"))
    )
    (net (code "124") (name "Net-(IC1-EECS)") (class "Default")
      (node (ref "IC1") (pin "63") (pinfunction "EECS_63") (pintype "output"))
      (node (ref "R10") (pin "1") (pinfunction "P$1_1") (pintype "passive"))
      (node (ref "U3") (pin "5") (pinfunction "CS_5") (pintype "input"))
    )
    (net (code "125") (name "Net-(IC1-EEDATA)") (class "Default")
      (node (ref "IC1") (pin "61") (pinfunction "EEDATA_61") (pintype "input"))
      (node (ref "R12") (pin "1") (pinfunction "P$1_1") (pintype "passive"))
      (node (ref "R13") (pin "1") (pinfunction "P$1_1") (pintype "passive"))
      (node (ref "U3") (pin "3") (pinfunction "DI_3") (pintype "input"))
    )
    (net (code "126") (name "Net-(IC1-EESK)") (class "Default")
      (node (ref "IC1") (pin "62") (pinfunction "EESK_62") (pintype "output"))
      (node (ref "R11") (pin "1") (pinfunction "P$1_1") (pintype "passive"))
      (node (ref "U3") (pin "4") (pinfunction "CLK_4") (pintype "input"))
    )
    (net (code "127") (name "Net-(IC1-REF)") (class "Default")
      (node (ref "IC1") (pin "6") (pinfunction "REF_6") (pintype "input"))
      (node (ref "R8") (pin "1") (pinfunction "P$1_1") (pintype "passive"))
    )
    (net (code "128") (name "Net-(R9-P$1)") (class "Default")
      (node (ref "R9") (pin "1") (pinfunction "P$1_1") (pintype "passive"))
      (node (ref "USB1") (pin "M6") (pinfunction "SHD_M6") (pintype "input"))
    )
    (net (code "129") (name "Net-(R13-P$2)") (class "Default")
      (node (ref "R13") (pin "2") (pinfunction "P$2_2") (pintype "passive"))
      (node (ref "U3") (pin "1") (pinfunction "DO_1") (pintype "output"))
    )
    (net (code "130") (name "Net-(R16-P$2)") (class "Default")
      (node (ref "R16") (pin "2") (pinfunction "P$2_2") (pintype "passive"))
      (node (ref "R17") (pin "1") (pinfunction "P$1_1") (pintype "passive"))
      (node (ref "U16") (pin "3") (pinfunction "+IN_3") (pintype "input"))
    )
    (net (code "131") (name "Net-(RN1A-2)") (class "Default")
      (node (ref "RN1") (pin "4") (pinfunction "1_4") (pintype "passive"))
      (node (ref "RN1") (pin "6") (pinfunction "2_6") (pintype "passive"))
      (node (ref "RN1") (pin "7") (pinfunction "2_7") (pintype "passive"))
      (node (ref "RN1") (pin "8") (pinfunction "2_8") (pintype "passive"))
      (node (ref "U8") (pin "13") (pinfunction "-IN_D_13") (pintype "input"))
    )
    (net (code "132") (name "Net-(RN1D-2)") (class "Default")
      (node (ref "AO2") (pin "1") (pinfunction "1_1") (pintype "passive"))
      (node (ref "RN1") (pin "5") (pinfunction "2_5") (pintype "passive"))
      (node (ref "U8") (pin "14") (pinfunction "OUT_D_14") (pintype "output"))
    )
    (net (code "133") (name "Net-(RN2A-2)") (class "Default")
      (node (ref "RN1") (pin "1") (pinfunction "1_1") (pintype "passive"))
      (node (ref "RN2") (pin "8") (pinfunction "2_8") (pintype "passive"))
      (node (ref "U7") (pin "6") (pinfunction "VOUT_6") (pintype "output"))
      (node (ref "U9") (pin "2") (pinfunction "VREFA_2") (pintype "input"))
      (node (ref "U9") (pin "7") (pinfunction "VREFB_7") (pintype "input"))
    )
    (net (code "134") (name "Net-(RN2B-1)") (class "Default")
      (node (ref "RN2") (pin "1") (pinfunction "1_1") (pintype "passive"))
      (node (ref "RN2") (pin "2") (pinfunction "1_2") (pintype "passive"))
      (node (ref "RN2") (pin "3") (pinfunction "1_3") (pintype "passive"))
      (node (ref "RN2") (pin "5") (pinfunction "2_5") (pintype "passive"))
      (node (ref "U8") (pin "9") (pinfunction "-IN_C_9") (pintype "input"))
    )
    (net (code "135") (name "Net-(RN2D-1)") (class "Default")
      (node (ref "AO1") (pin "1") (pinfunction "1_1") (pintype "passive"))
      (node (ref "RN2") (pin "4") (pinfunction "1_4") (pintype "passive"))
      (node (ref "U8") (pin "8") (pinfunction "OUT_C_8") (pintype "output"))
    )
    (net (code "136") (name "Net-(RN3A-2)") (class "Default")
      (node (ref "RN3") (pin "4") (pinfunction "1_4") (pintype "passive"))
      (node (ref "RN3") (pin "6") (pinfunction "2_6") (pintype "passive"))
      (node (ref "RN3") (pin "7") (pinfunction "2_7") (pintype "passive"))
      (node (ref "RN3") (pin "8") (pinfunction "2_8") (pintype "passive"))
      (node (ref "U11") (pin "13") (pinfunction "-IN_D_13") (pintype "input"))
    )
    (net (code "137") (name "Net-(RN3D-2)") (class "Default")
      (node (ref "AO4") (pin "1") (pinfunction "1_1") (pintype "passive"))
      (node (ref "RN3") (pin "5") (pinfunction "2_5") (pintype "passive"))
      (node (ref "U11") (pin "14") (pinfunction "OUT_D_14") (pintype "output"))
    )
    (net (code "138") (name "Net-(RN4A-2)") (class "Default")
      (node (ref "RN3") (pin "1") (pinfunction "1_1") (pintype "passive"))
      (node (ref "RN4") (pin "8") (pinfunction "2_8") (pintype "passive"))
      (node (ref "U10") (pin "6") (pinfunction "VOUT_6") (pintype "output"))
      (node (ref "U12") (pin "2") (pinfunction "VREFA_2") (pintype "input"))
      (node (ref "U12") (pin "7") (pinfunction "VREFB_7") (pintype "input"))
    )
    (net (code "139") (name "Net-(RN4B-1)") (class "Default")
      (node (ref "RN4") (pin "1") (pinfunction "1_1") (pintype "passive"))
      (node (ref "RN4") (pin "2") (pinfunction "1_2") (pintype "passive"))
      (node (ref "RN4") (pin "3") (pinfunction "1_3") (pintype "passive"))
      (node (ref "RN4") (pin "5") (pinfunction "2_5") (pintype "passive"))
      (node (ref "U11") (pin "9") (pinfunction "-IN_C_9") (pintype "input"))
    )
    (net (code "140") (name "Net-(RN4D-1)") (class "Default")
      (node (ref "AO3") (pin "1") (pinfunction "1_1") (pintype "passive"))
      (node (ref "RN4") (pin "4") (pinfunction "1_4") (pintype "passive"))
      (node (ref "U11") (pin "8") (pinfunction "OUT_C_8") (pintype "output"))
    )
    (net (code "141") (name "Net-(RN5A-2)") (class "Default")
      (node (ref "RN5") (pin "4") (pinfunction "1_4") (pintype "passive"))
      (node (ref "RN5") (pin "6") (pinfunction "2_6") (pintype "passive"))
      (node (ref "RN5") (pin "7") (pinfunction "2_7") (pintype "passive"))
      (node (ref "RN5") (pin "8") (pinfunction "2_8") (pintype "passive"))
      (node (ref "U14") (pin "13") (pinfunction "-IN_D_13") (pintype "input"))
    )
    (net (code "142") (name "Net-(RN5D-2)") (class "Default")
      (node (ref "AO6") (pin "1") (pinfunction "1_1") (pintype "passive"))
      (node (ref "RN5") (pin "5") (pinfunction "2_5") (pintype "passive"))
      (node (ref "U14") (pin "14") (pinfunction "OUT_D_14") (pintype "output"))
    )
    (net (code "143") (name "Net-(RN6A-2)") (class "Default")
      (node (ref "RN5") (pin "1") (pinfunction "1_1") (pintype "passive"))
      (node (ref "RN6") (pin "8") (pinfunction "2_8") (pintype "passive"))
      (node (ref "U13") (pin "6") (pinfunction "VOUT_6") (pintype "output"))
      (node (ref "U15") (pin "2") (pinfunction "VREFA_2") (pintype "input"))
      (node (ref "U15") (pin "7") (pinfunction "VREFB_7") (pintype "input"))
    )
    (net (code "144") (name "Net-(RN6B-1)") (class "Default")
      (node (ref "RN6") (pin "1") (pinfunction "1_1") (pintype "passive"))
      (node (ref "RN6") (pin "2") (pinfunction "1_2") (pintype "passive"))
      (node (ref "RN6") (pin "3") (pinfunction "1_3") (pintype "passive"))
      (node (ref "RN6") (pin "5") (pinfunction "2_5") (pintype "passive"))
      (node (ref "U14") (pin "9") (pinfunction "-IN_C_9") (pintype "input"))
    )
    (net (code "145") (name "Net-(RN6D-1)") (class "Default")
      (node (ref "AO5") (pin "1") (pinfunction "1_1") (pintype "passive"))
      (node (ref "RN6") (pin "4") (pinfunction "1_4") (pintype "passive"))
      (node (ref "U14") (pin "8") (pinfunction "OUT_C_8") (pintype "output"))
    )
    (net (code "146") (name "Net-(U1-SW)") (class "Default")
      (node (ref "L1") (pin "1") (pinfunction "1_1") (pintype "passive"))
      (node (ref "U1") (pin "5") (pinfunction "SW_5") (pintype "output"))
    )
    (net (code "147") (name "Net-(U2-SW)") (class "Default")
      (node (ref "L2") (pin "1") (pinfunction "1_1") (pintype "passive"))
      (node (ref "U2") (pin "5") (pinfunction "SW_5") (pintype "output"))
    )
    (net (code "148") (name "unconnected-(IC1--PWREN-Pad60)") (class "Default")
      (node (ref "IC1") (pin "60") (pinfunction "-PWREN_60") (pintype "output"))
    )
    (net (code "149") (name "unconnected-(IC1--SUSPEND-Pad36)") (class "Default")
      (node (ref "IC1") (pin "36") (pinfunction "-SUSPEND_36") (pintype "output"))
    )
    (net (code "150") (name "unconnected-(IC1-ACBUS7-Pad34)") (class "Default")
      (node (ref "IC1") (pin "34") (pinfunction "ACBUS7_34") (pintype "bidirectional"))
    )
    (net (code "151") (name "unconnected-(IC1-BCBUS0-Pad48)") (class "Default")
      (node (ref "IC1") (pin "48") (pinfunction "BCBUS0_48") (pintype "bidirectional"))
    )
    (net (code "152") (name "unconnected-(IC1-BCBUS1-Pad52)") (class "Default")
      (node (ref "IC1") (pin "52") (pinfunction "BCBUS1_52") (pintype "bidirectional"))
    )
    (net (code "153") (name "unconnected-(IC1-BCBUS2-Pad53)") (class "Default")
      (node (ref "IC1") (pin "53") (pinfunction "BCBUS2_53") (pintype "bidirectional"))
    )
    (net (code "154") (name "unconnected-(IC1-BCBUS3-Pad54)") (class "Default")
      (node (ref "IC1") (pin "54") (pinfunction "BCBUS3_54") (pintype "bidirectional"))
    )
    (net (code "155") (name "unconnected-(IC1-BCBUS4-Pad55)") (class "Default")
      (node (ref "IC1") (pin "55") (pinfunction "BCBUS4_55") (pintype "bidirectional"))
    )
    (net (code "156") (name "unconnected-(IC1-BCBUS5-Pad57)") (class "Default")
      (node (ref "IC1") (pin "57") (pinfunction "BCBUS5_57") (pintype "bidirectional"))
    )
    (net (code "157") (name "unconnected-(IC1-BCBUS6-Pad58)") (class "Default")
      (node (ref "IC1") (pin "58") (pinfunction "BCBUS6_58") (pintype "bidirectional"))
    )
    (net (code "158") (name "unconnected-(IC1-BDBUS4-Pad43)") (class "Default")
      (node (ref "IC1") (pin "43") (pinfunction "BDBUS4_43") (pintype "bidirectional"))
    )
    (net (code "159") (name "unconnected-(IC1-BDBUS5-Pad44)") (class "Default")
      (node (ref "IC1") (pin "44") (pinfunction "BDBUS5_44") (pintype "bidirectional"))
    )
    (net (code "160") (name "unconnected-(IC1-BDBUS6-Pad45)") (class "Default")
      (node (ref "IC1") (pin "45") (pinfunction "BDBUS6_45") (pintype "bidirectional"))
    )
    (net (code "161") (name "unconnected-(IC1-BDBUS7-Pad46)") (class "Default")
      (node (ref "IC1") (pin "46") (pinfunction "BDBUS7_46") (pintype "bidirectional"))
    )
    (net (code "162") (name "unconnected-(IC1-PWRSAVE{slash}BCBUS7-Pad59)") (class "Default")
      (node (ref "IC1") (pin "59") (pinfunction "PWRSAVE/BCBUS7_59") (pintype "bidirectional"))
    )
    (net (code "163") (name "unconnected-(IC2A-NC-Pad40)") (class "Default")
      (node (ref "IC2") (pin "40") (pinfunction "NC_40") (pintype "no_connect"))
    )
    (net (code "164") (name "unconnected-(U4B-IO_L74N_DOUT_BUSY_1-Pad74)") (class "Default")
      (node (ref "U4") (pin "74") (pinfunction "IO_L74N_DOUT_BUSY_1_74") (pintype "bidirectional"))
    )
    (net (code "165") (name "unconnected-(U4B-IO_L74P_AWAKE_1-Pad75)") (class "Default")
      (node (ref "U4") (pin "75") (pinfunction "IO_L74P_AWAKE_1_75") (pintype "bidirectional"))
    )
    (net (code "166") (name "unconnected-(U4C-CMPCS_B_2-Pad72)") (class "Default")
      (node (ref "U4") (pin "72") (pinfunction "CMPCS_B_2_72") (pintype "bidirectional"))
    )
    (net (code "167") (name "unconnected-(U4C-DONE_2-Pad71)") (class "Default")
      (node (ref "U4") (pin "71") (pinfunction "DONE_2_71") (pintype "bidirectional"))
    )
    (net (code "168") (name "unconnected-(U4C-IO_L65P_INIT_B_2-Pad39)") (class "Default")
      (node (ref "U4") (pin "39") (pinfunction "IO_L65P_INIT_B_2_39") (pintype "bidirectional"))
    )
    (net (code "169") (name "unconnected-(U7-NC-Pad7)") (class "Default")
      (node (ref "U7") (pin "7") (pinfunction "NC_7") (pintype "no_connect"))
    )
    (net (code "170") (name "unconnected-(U7-NC_2-Pad1)") (class "Default")
      (node (ref "U7") (pin "1") (pinfunction "NC_2_1") (pintype "no_connect"))
    )
    (net (code "171") (name "unconnected-(U7-NC_3-Pad3)") (class "Default")
      (node (ref "U7") (pin "3") (pinfunction "NC_3_3") (pintype "no_connect"))
    )
    (net (code "172") (name "unconnected-(U7-TRIM-Pad5)") (class "Default")
      (node (ref "U7") (pin "5") (pinfunction "TRIM_5") (pintype "passive"))
    )
    (net (code "173") (name "unconnected-(U10-NC-Pad7)") (class "Default")
      (node (ref "U10") (pin "7") (pinfunction "NC_7") (pintype "no_connect"))
    )
    (net (code "174") (name "unconnected-(U10-NC_2-Pad1)") (class "Default")
      (node (ref "U10") (pin "1") (pinfunction "NC_2_1") (pintype "no_connect"))
    )
    (net (code "175") (name "unconnected-(U10-NC_3-Pad3)") (class "Default")
      (node (ref "U10") (pin "3") (pinfunction "NC_3_3") (pintype "no_connect"))
    )
    (net (code "176") (name "unconnected-(U10-TRIM-Pad5)") (class "Default")
      (node (ref "U10") (pin "5") (pinfunction "TRIM_5") (pintype "passive"))
    )
    (net (code "177") (name "unconnected-(U13-NC-Pad7)") (class "Default")
      (node (ref "U13") (pin "7") (pinfunction "NC_7") (pintype "no_connect"))
    )
    (net (code "178") (name "unconnected-(U13-NC_2-Pad1)") (class "Default")
      (node (ref "U13") (pin "1") (pinfunction "NC_2_1") (pintype "no_connect"))
    )
    (net (code "179") (name "unconnected-(U13-NC_3-Pad3)") (class "Default")
      (node (ref "U13") (pin "3") (pinfunction "NC_3_3") (pintype "no_connect"))
    )
    (net (code "180") (name "unconnected-(U13-TRIM-Pad5)") (class "Default")
      (node (ref "U13") (pin "5") (pinfunction "TRIM_5") (pintype "passive"))
    )
    (net (code "181") (name "unconnected-(USB1-ID-Pad4)") (class "Default")
      (node (ref "USB1") (pin "4") (pinfunction "ID_4") (pintype "input"))
    )
    (net (code "182") (name "unconnected-(USB1-SHD-PadM1)") (class "Default")
      (node (ref "USB1") (pin "M1") (pinfunction "SHD_M1") (pintype "input"))
    )
    (net (code "183") (name "unconnected-(USB1-SHD-PadM2)") (class "Default")
      (node (ref "USB1") (pin "M2") (pinfunction "SHD_M2") (pintype "input"))
    )
    (net (code "184") (name "unconnected-(USB1-SHD-PadM3)") (class "Default")
      (node (ref "USB1") (pin "M3") (pinfunction "SHD_M3") (pintype "input"))
    )
  )
)
